# EDCPSUMK2-RP2040.net
KiCad netlist of a schematic drawn in EAGLE
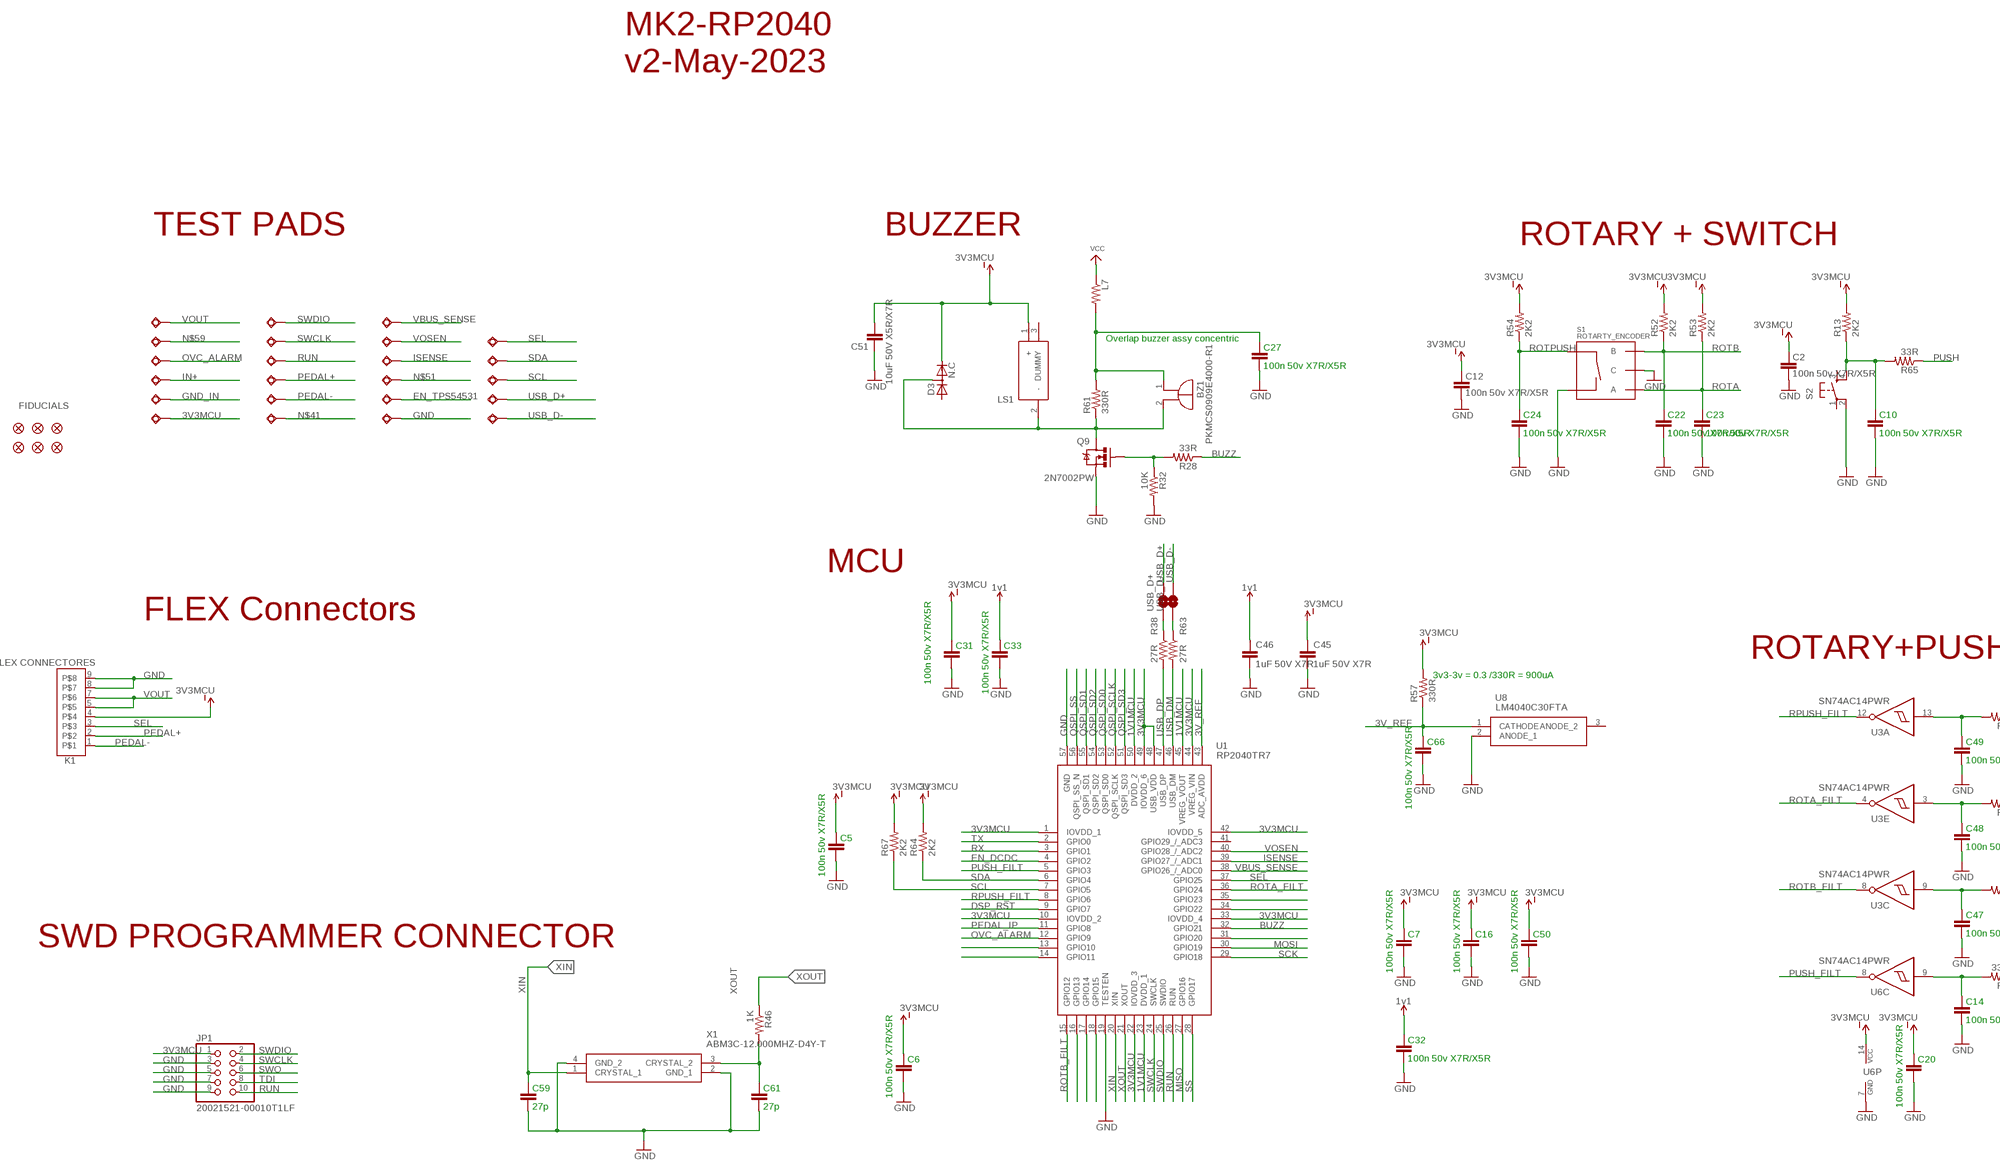
[diagram p0: schematic, sheet 1, part 1 of 3]
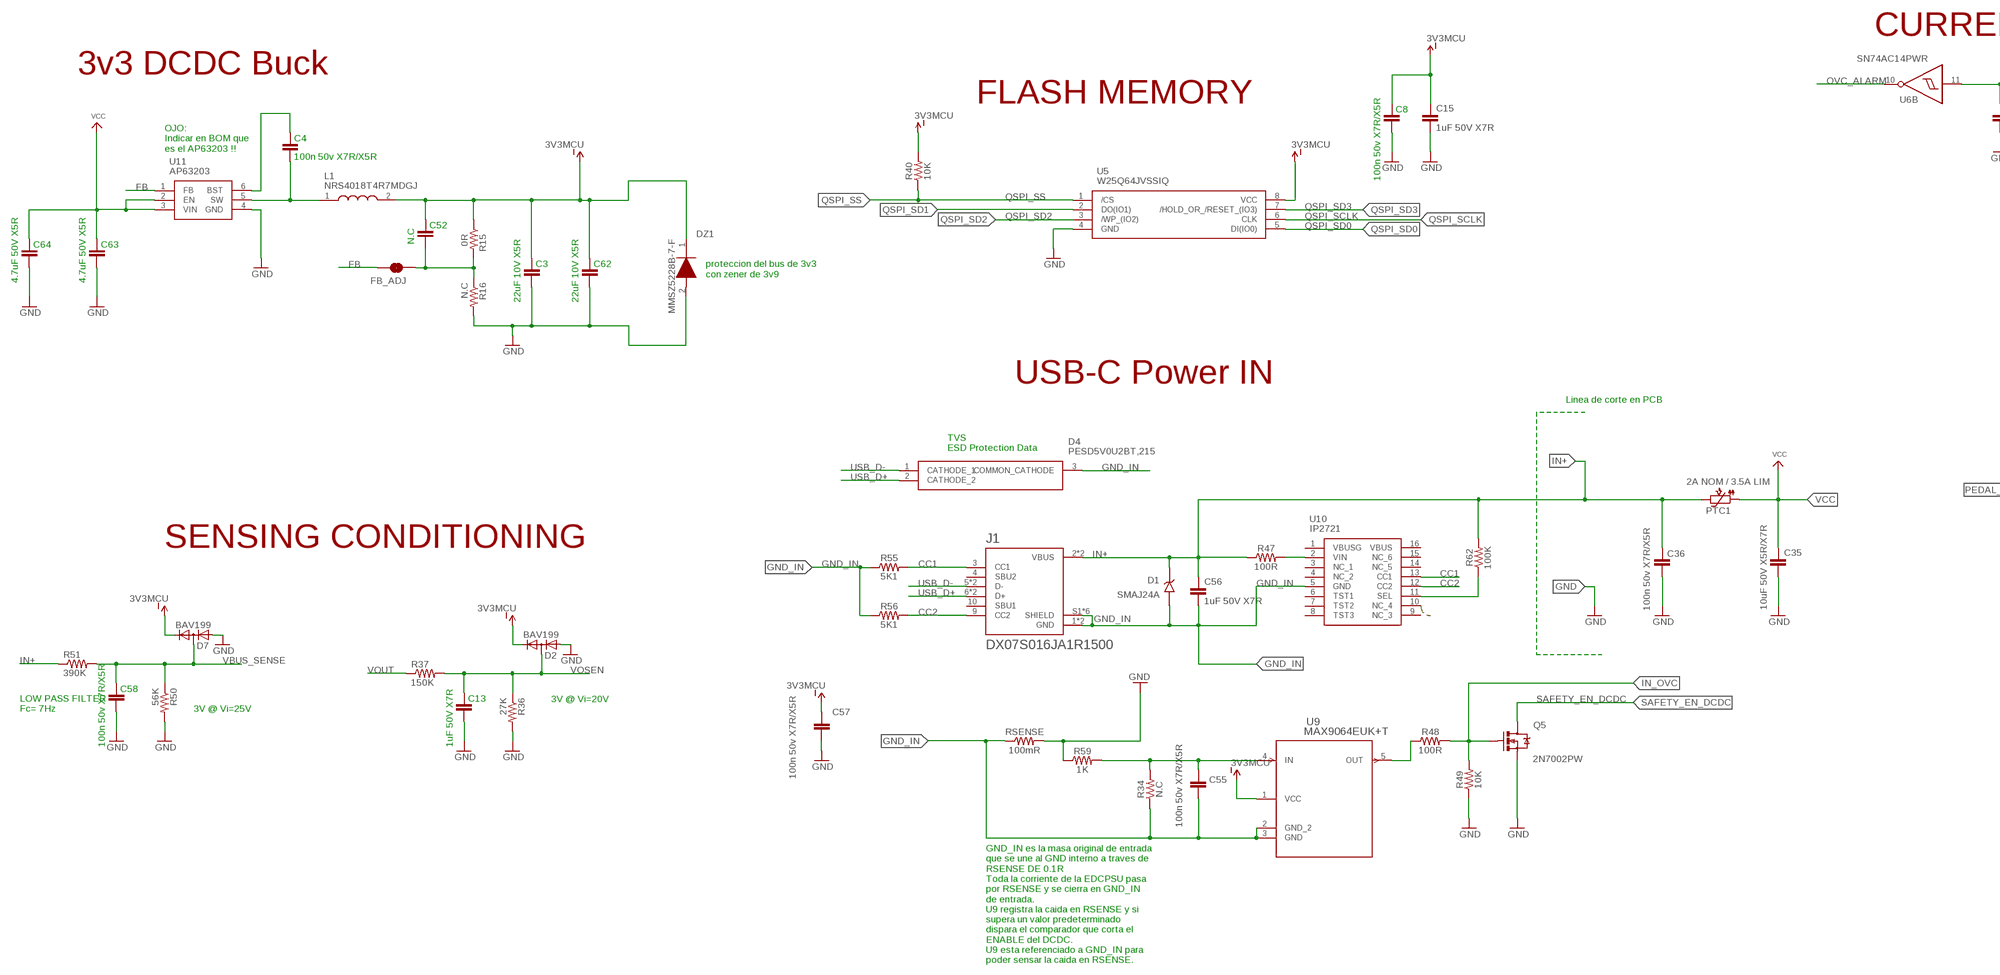
[diagram p1: schematic, sheet 1, part 2 of 3]
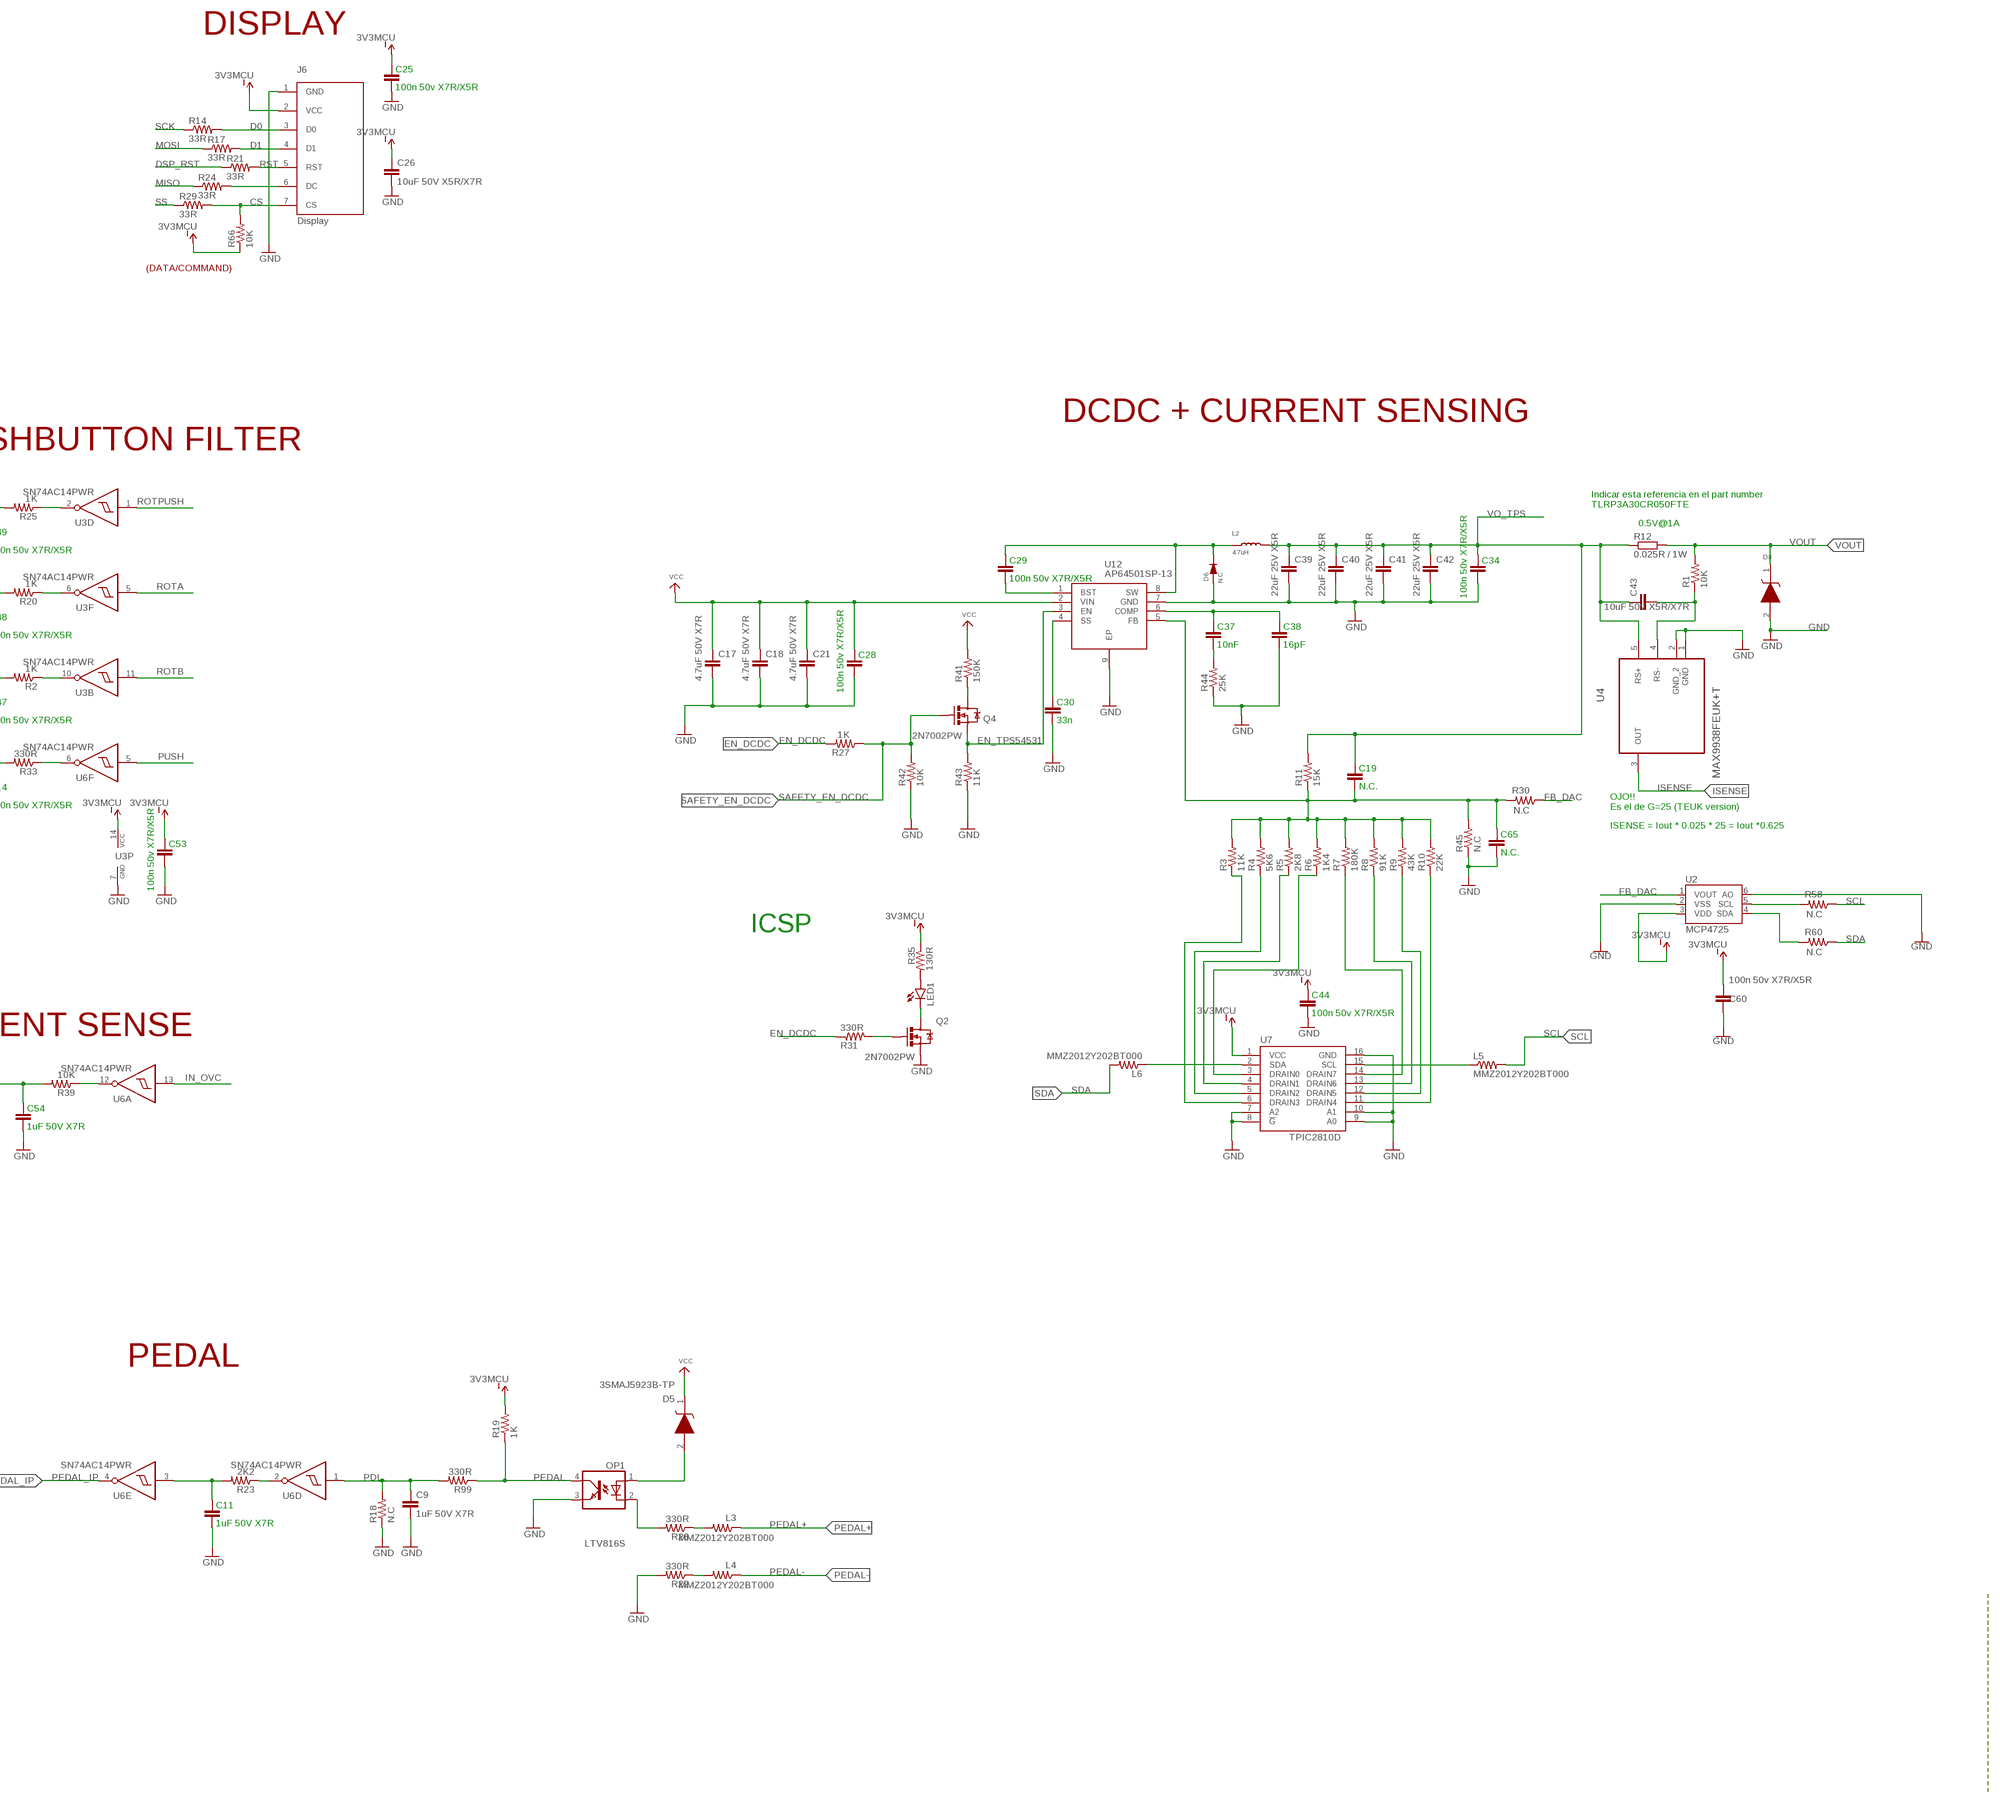
[diagram p2: schematic, sheet 1, part 3 of 3]

(export (version "E")
  (design (tool "Eeschema 10.0.6"))
  (components
    (comp (ref "3V3MCU")
      (value "TESTPAD_TPSQB1,27")
      (footprint "eagle-import:TESTPAD_B1,27")
      (libsource (lib "eagle-import") (part "TESTPAD_TPSQB1,27"))
    )
    (comp (ref "BZ1")
      (value "PKMCS0909E4000-R1")
      (footprint "eagle-import:PKMCS0909")
      (libsource (lib "eagle-import") (part "PKMCS0909E4000-R1"))
    )
    (comp (ref "C2")
      (value "100n 50v X7R/X5R")
      (footprint "eagle-import:0805")
      (libsource (lib "eagle-import") (part "CAP0805"))
    )
    (comp (ref "C3")
      (value "22uF 10V X5R")
      (footprint "eagle-import:0805")
      (libsource (lib "eagle-import") (part "CAP0805"))
    )
    (comp (ref "C4")
      (value "100n 50v X7R/X5R")
      (footprint "eagle-import:0805")
      (libsource (lib "eagle-import") (part "CAP0805"))
    )
    (comp (ref "C5")
      (value "100n 50v X7R/X5R")
      (footprint "eagle-import:0805")
      (libsource (lib "eagle-import") (part "CAP0805"))
    )
    (comp (ref "C6")
      (value "100n 50v X7R/X5R")
      (footprint "eagle-import:0805")
      (libsource (lib "eagle-import") (part "CAP0805"))
    )
    (comp (ref "C7")
      (value "100n 50v X7R/X5R")
      (footprint "eagle-import:0805")
      (libsource (lib "eagle-import") (part "CAP0805"))
    )
    (comp (ref "C8")
      (value "100n 50v X7R/X5R")
      (footprint "eagle-import:0805")
      (libsource (lib "eagle-import") (part "CAP0805"))
    )
    (comp (ref "C9")
      (value "1uF 50V X7R")
      (footprint "eagle-import:0805")
      (libsource (lib "eagle-import") (part "CAP0805"))
    )
    (comp (ref "C10")
      (value "100n 50v X7R/X5R")
      (footprint "eagle-import:0805")
      (libsource (lib "eagle-import") (part "CAP0805"))
    )
    (comp (ref "C11")
      (value "1uF 50V X7R")
      (footprint "eagle-import:0805")
      (libsource (lib "eagle-import") (part "CAP0805"))
    )
    (comp (ref "C12")
      (value "100n 50v X7R/X5R")
      (footprint "eagle-import:0805")
      (libsource (lib "eagle-import") (part "CAP0805"))
    )
    (comp (ref "C13")
      (value "1uF 50V X7R")
      (footprint "eagle-import:0805")
      (libsource (lib "eagle-import") (part "CAP0805"))
    )
    (comp (ref "C14")
      (value "100n 50v X7R/X5R")
      (footprint "eagle-import:0805")
      (libsource (lib "eagle-import") (part "CAP0805"))
    )
    (comp (ref "C15")
      (value "1uF 50V X7R")
      (footprint "eagle-import:0805")
      (libsource (lib "eagle-import") (part "CAP0805"))
    )
    (comp (ref "C16")
      (value "100n 50v X7R/X5R")
      (footprint "eagle-import:0805")
      (libsource (lib "eagle-import") (part "CAP0805"))
    )
    (comp (ref "C17")
      (value "4.7uF 50V X7R")
      (footprint "eagle-import:1210")
      (libsource (lib "eagle-import") (part "CAP1210"))
    )
    (comp (ref "C18")
      (value "4.7uF 50V X7R")
      (footprint "eagle-import:1210")
      (libsource (lib "eagle-import") (part "CAP1210"))
    )
    (comp (ref "C19")
      (value "N.C.")
      (footprint "eagle-import:0805")
      (libsource (lib "eagle-import") (part "CAP0805"))
    )
    (comp (ref "C20")
      (value "100n 50v X7R/X5R")
      (footprint "eagle-import:0805")
      (libsource (lib "eagle-import") (part "CAP0805"))
    )
    (comp (ref "C21")
      (value "4.7uF 50V X7R")
      (footprint "eagle-import:1210")
      (libsource (lib "eagle-import") (part "CAP1210"))
    )
    (comp (ref "C22")
      (value "100n 50v X7R/X5R")
      (footprint "eagle-import:0805")
      (libsource (lib "eagle-import") (part "CAP0805"))
    )
    (comp (ref "C23")
      (value "100n 50v X7R/X5R")
      (footprint "eagle-import:0805")
      (libsource (lib "eagle-import") (part "CAP0805"))
    )
    (comp (ref "C24")
      (value "100n 50v X7R/X5R")
      (footprint "eagle-import:0805")
      (libsource (lib "eagle-import") (part "CAP0805"))
    )
    (comp (ref "C25")
      (value "100n 50v X7R/X5R")
      (footprint "eagle-import:0805")
      (libsource (lib "eagle-import") (part "CAP0805"))
    )
    (comp (ref "C26")
      (value "10uF 50V X5R/X7R")
      (footprint "eagle-import:1206")
      (libsource (lib "eagle-import") (part "CAP1206"))
    )
    (comp (ref "C27")
      (value "100n 50v X7R/X5R")
      (footprint "eagle-import:0805")
      (libsource (lib "eagle-import") (part "CAP0805"))
    )
    (comp (ref "C28")
      (value "100n 50v X7R/X5R")
      (footprint "eagle-import:0805")
      (libsource (lib "eagle-import") (part "CAP0805"))
    )
    (comp (ref "C29")
      (value "100n 50v X7R/X5R")
      (footprint "eagle-import:0805")
      (libsource (lib "eagle-import") (part "CAP0805"))
    )
    (comp (ref "C30")
      (value "33n")
      (footprint "eagle-import:0805")
      (libsource (lib "eagle-import") (part "CAP0805"))
    )
    (comp (ref "C31")
      (value "100n 50v X7R/X5R")
      (footprint "eagle-import:0805")
      (libsource (lib "eagle-import") (part "CAP0805"))
    )
    (comp (ref "C32")
      (value "100n 50v X7R/X5R")
      (footprint "eagle-import:0805")
      (libsource (lib "eagle-import") (part "CAP0805"))
    )
    (comp (ref "C33")
      (value "100n 50v X7R/X5R")
      (footprint "eagle-import:0805")
      (libsource (lib "eagle-import") (part "CAP0805"))
    )
    (comp (ref "C34")
      (value "100n 50v X7R/X5R")
      (footprint "eagle-import:0805")
      (libsource (lib "eagle-import") (part "CAP0805"))
    )
    (comp (ref "C35")
      (value "10uF 50V X5R/X7R")
      (footprint "eagle-import:1206")
      (libsource (lib "eagle-import") (part "CAP1206"))
    )
    (comp (ref "C36")
      (value "100n 50v X7R/X5R")
      (footprint "eagle-import:0805")
      (libsource (lib "eagle-import") (part "CAP0805"))
    )
    (comp (ref "C37")
      (value "10nF")
      (footprint "eagle-import:0805")
      (libsource (lib "eagle-import") (part "CAP0805"))
    )
    (comp (ref "C38")
      (value "16pF")
      (footprint "eagle-import:0805")
      (libsource (lib "eagle-import") (part "CAP0805"))
    )
    (comp (ref "C39")
      (value "22uF 25V X5R")
      (footprint "eagle-import:1210")
      (libsource (lib "eagle-import") (part "CAP1210"))
    )
    (comp (ref "C40")
      (value "22uF 25V X5R")
      (footprint "eagle-import:1210")
      (libsource (lib "eagle-import") (part "CAP1210"))
    )
    (comp (ref "C41")
      (value "22uF 25V X5R")
      (footprint "eagle-import:1210")
      (libsource (lib "eagle-import") (part "CAP1210"))
    )
    (comp (ref "C42")
      (value "22uF 25V X5R")
      (footprint "eagle-import:1210")
      (libsource (lib "eagle-import") (part "CAP1210"))
    )
    (comp (ref "C43")
      (value "10uF 50V X5R/X7R")
      (footprint "eagle-import:1206")
      (libsource (lib "eagle-import") (part "CAP1206"))
    )
    (comp (ref "C44")
      (value "100n 50v X7R/X5R")
      (footprint "eagle-import:0805")
      (libsource (lib "eagle-import") (part "CAP0805"))
    )
    (comp (ref "C45")
      (value "1uF 50V X7R")
      (footprint "eagle-import:0805")
      (libsource (lib "eagle-import") (part "CAP0805"))
    )
    (comp (ref "C46")
      (value "1uF 50V X7R")
      (footprint "eagle-import:0805")
      (libsource (lib "eagle-import") (part "CAP0805"))
    )
    (comp (ref "C47")
      (value "100n 50v X7R/X5R")
      (footprint "eagle-import:0805")
      (libsource (lib "eagle-import") (part "CAP0805"))
    )
    (comp (ref "C48")
      (value "100n 50v X7R/X5R")
      (footprint "eagle-import:0805")
      (libsource (lib "eagle-import") (part "CAP0805"))
    )
    (comp (ref "C49")
      (value "100n 50v X7R/X5R")
      (footprint "eagle-import:0805")
      (libsource (lib "eagle-import") (part "CAP0805"))
    )
    (comp (ref "C50")
      (value "100n 50v X7R/X5R")
      (footprint "eagle-import:0805")
      (libsource (lib "eagle-import") (part "CAP0805"))
    )
    (comp (ref "C51")
      (value "10uF 50V X5R/X7R")
      (footprint "eagle-import:1206")
      (libsource (lib "eagle-import") (part "CAP1206"))
    )
    (comp (ref "C52")
      (value "N.C")
      (footprint "eagle-import:0805")
      (libsource (lib "eagle-import") (part "CAP0805"))
    )
    (comp (ref "C53")
      (value "100n 50v X7R/X5R")
      (footprint "eagle-import:0805")
      (libsource (lib "eagle-import") (part "CAP0805"))
    )
    (comp (ref "C54")
      (value "1uF 50V X7R")
      (footprint "eagle-import:0805")
      (libsource (lib "eagle-import") (part "CAP0805"))
    )
    (comp (ref "C55")
      (value "100n 50v X7R/X5R")
      (footprint "eagle-import:0805")
      (libsource (lib "eagle-import") (part "CAP0805"))
    )
    (comp (ref "C56")
      (value "1uF 50V X7R")
      (footprint "eagle-import:0805")
      (libsource (lib "eagle-import") (part "CAP0805"))
    )
    (comp (ref "C57")
      (value "100n 50v X7R/X5R")
      (footprint "eagle-import:0805")
      (libsource (lib "eagle-import") (part "CAP0805"))
    )
    (comp (ref "C58")
      (value "100n 50v X7R/X5R")
      (footprint "eagle-import:0805")
      (libsource (lib "eagle-import") (part "CAP0805"))
    )
    (comp (ref "C59")
      (value "27p")
      (footprint "eagle-import:0805")
      (libsource (lib "eagle-import") (part "CAP0805"))
    )
    (comp (ref "C60")
      (value "100n 50v X7R/X5R")
      (footprint "eagle-import:0805")
      (libsource (lib "eagle-import") (part "CAP0805"))
    )
    (comp (ref "C61")
      (value "27p")
      (footprint "eagle-import:0805")
      (libsource (lib "eagle-import") (part "CAP0805"))
    )
    (comp (ref "C62")
      (value "22uF 10V X5R")
      (footprint "eagle-import:0805")
      (libsource (lib "eagle-import") (part "CAP0805"))
    )
    (comp (ref "C63")
      (value "4.7uF 50V X5R")
      (footprint "eagle-import:0805")
      (libsource (lib "eagle-import") (part "CAP0805"))
    )
    (comp (ref "C64")
      (value "4.7uF 50V X5R")
      (footprint "eagle-import:0805")
      (libsource (lib "eagle-import") (part "CAP0805"))
    )
    (comp (ref "C65")
      (value "N.C.")
      (footprint "eagle-import:0805")
      (libsource (lib "eagle-import") (part "CAP0805"))
    )
    (comp (ref "C66")
      (value "100n 50v X7R/X5R")
      (footprint "eagle-import:0805")
      (libsource (lib "eagle-import") (part "CAP0805"))
    )
    (comp (ref "D1")
      (value "SMAJ24A")
      (footprint "eagle-import:DIOM4325X244N")
      (fields (field (name "MF") "Micro Commercial Components") (field (name "MP") "3SMAJ5934B"))
      (libsource (lib "eagle-import") (part "3SMAJ5934B"))
    )
    (comp (ref "D2")
      (value "BAV199")
      (footprint "eagle-import:SOT23")
      (libsource (lib "eagle-import") (part "BAV199"))
    )
    (comp (ref "D3")
      (value "N.C")
      (footprint "eagle-import:SOT23")
      (libsource (lib "eagle-import") (part "BAV199"))
    )
    (comp (ref "D4")
      (value "PESD5V0U2BT,215")
      (footprint "eagle-import:SOT95P230X110-3N")
      (fields (field (name "MOUSER_PART_NUMBER") "771-PESD5V0U2BTT/R"))
      (libsource (lib "eagle-import") (part "PESD5V0U2BT,215"))
    )
    (comp (ref "D5")
      (value "3SMAJ5923B-TP")
      (footprint "eagle-import:DIOM5226X244N")
      (fields (field (name "MOUSER_PART_NUMBER") "833-3SMAJ5923B-TP"))
      (libsource (lib "eagle-import") (part "3SMAJ5923B-TP"))
    )
    (comp (ref "D6")
      (value "N.C")
      (footprint "eagle-import:DO-214AB")
      (libsource (lib "eagle-import") (part "DSMC"))
    )
    (comp (ref "D7")
      (value "BAV199")
      (footprint "eagle-import:SOT23")
      (libsource (lib "eagle-import") (part "BAV199"))
    )
    (comp (ref "D8")
      (value "RB060M-60TR")
      (footprint "eagle-import:DIOM5226X244N")
      (fields
        (field (name "ARROW_PART_NUMBER") "3SMAJ5923B-TP")
        (field (name "MOUSER_PART_NUMBER") "833-3SMAJ5923B-TP")
      )
      (libsource (lib "eagle-import") (part "3SMAJ5923B-TP"))
    )
    (comp (ref "DZ1")
      (value "MMSZ5228B-7-F")
      (footprint "eagle-import:SODFL3518X115N")
      (libsource (lib "eagle-import") (part "MMSZ5228B-7-F"))
    )
    (comp (ref "EN_TPS54531")
      (value "TESTPAD_TPSQB1,27")
      (footprint "eagle-import:TESTPAD_B1,27")
      (libsource (lib "eagle-import") (part "TESTPAD_TPSQB1,27"))
    )
    (comp (ref "FB_ADJ")
      (value "JUMPER-SMT_2_NC_TRACE_NO-SILK")
      (footprint "eagle-import:SMT-JUMPER_2_NC_TRACE_NO-SILK")
      (libsource (lib "eagle-import") (part "JUMPER-SMT_2_NC_TRACE_NO-SILK"))
    )
    (comp (ref "FID1")
      (value "FIDUCIAL1X2")
      (footprint "eagle-import:FIDUCIAL-1X2")
      (libsource (lib "eagle-import") (part "FIDUCIAL1X2"))
    )
    (comp (ref "FID2")
      (value "FIDUCIAL1X2")
      (footprint "eagle-import:FIDUCIAL-1X2")
      (libsource (lib "eagle-import") (part "FIDUCIAL1X2"))
    )
    (comp (ref "FID3")
      (value "FIDUCIAL1X2")
      (footprint "eagle-import:FIDUCIAL-1X2")
      (libsource (lib "eagle-import") (part "FIDUCIAL1X2"))
    )
    (comp (ref "FID4")
      (value "FIDUCIAL1X2")
      (footprint "eagle-import:FIDUCIAL-1X2")
      (libsource (lib "eagle-import") (part "FIDUCIAL1X2"))
    )
    (comp (ref "FID5")
      (value "FIDUCIAL1X2")
      (footprint "eagle-import:FIDUCIAL-1X2")
      (libsource (lib "eagle-import") (part "FIDUCIAL1X2"))
    )
    (comp (ref "FID6")
      (value "FIDUCIAL1X2")
      (footprint "eagle-import:FIDUCIAL-1X2")
      (libsource (lib "eagle-import") (part "FIDUCIAL1X2"))
    )
    (comp (ref "GND")
      (value "TESTPAD_TPSQB1,27")
      (footprint "eagle-import:TESTPAD_B1,27")
      (libsource (lib "eagle-import") (part "TESTPAD_TPSQB1,27"))
    )
    (comp (ref "GND_IN")
      (value "TESTPAD_TPSQB1,27")
      (footprint "eagle-import:TESTPAD_B1,27")
      (libsource (lib "eagle-import") (part "TESTPAD_TPSQB1,27"))
    )
    (comp (ref "IN+")
      (value "TESTPAD_TPSQB1,27")
      (footprint "eagle-import:TESTPAD_B1,27")
      (libsource (lib "eagle-import") (part "TESTPAD_TPSQB1,27"))
    )
    (comp (ref "ISENSE")
      (value "TESTPAD_TPSQB1,27")
      (footprint "eagle-import:TESTPAD_B1,27")
      (libsource (lib "eagle-import") (part "TESTPAD_TPSQB1,27"))
    )
    (comp (ref "J1")
      (value "DX07S016JA1R1500")
      (footprint "eagle-import:JAE_DX07S016JA1R1500")
      (fields
        (field (name "DIGI-KEY_PART_NUMBER") "670-DX07S016JA1R1500CT-ND")
        (field (name "MF") "JAE Electronics")
      )
      (libsource (lib "eagle-import") (part "DX07S016JA1R1500"))
    )
    (comp (ref "J6")
      (value "Display")
      (footprint "eagle-import:OLED_LCD")
      (libsource (lib "eagle-import") (part "OLED_LCD"))
    )
    (comp (ref "JP1")
      (value "20021521-00010T1LF")
      (footprint "eagle-import:20021521-00010T1LF")
      (fields (field (name "DIGI-KEY_PART_NUMBER") "609-4054-ND") (field (name "MF") "AMPHENOL ICC / FCI"))
      (libsource (lib "eagle-import") (part "20021521-00010T1LF"))
    )
    (comp (ref "K1")
      (value "FLEX CONNECTORES")
      (footprint "eagle-import:FLEX8")
      (libsource (lib "eagle-import") (part "FLEX8"))
    )
    (comp (ref "L1")
      (value "NRS4018T4R7MDGJ")
      (footprint "eagle-import:NRS4018T100MDGJ")
      (fields (field (name "MOUSER_PART_NUMBER") "963-NRS4018T4R7MDGJ"))
      (libsource (lib "eagle-import") (part "NRS4018T4R7MDGJ"))
    )
    (comp (ref "L2")
      (value "4.7uH")
      (footprint "eagle-import:WE-LHMI")
      (libsource (lib "eagle-import") (part "L74437368047"))
    )
    (comp (ref "L3")
      (value "MMZ2012Y202BT000")
      (footprint "eagle-import:0805")
      (libsource (lib "eagle-import") (part "RESISTOR0805-RES"))
    )
    (comp (ref "L4")
      (value "MMZ2012Y202BT000")
      (footprint "eagle-import:0805")
      (libsource (lib "eagle-import") (part "RESISTOR0805-RES"))
    )
    (comp (ref "L5")
      (value "MMZ2012Y202BT000")
      (footprint "eagle-import:0805")
      (libsource (lib "eagle-import") (part "RESISTOR0805-RES"))
    )
    (comp (ref "L6")
      (value "MMZ2012Y202BT000")
      (footprint "eagle-import:0805")
      (libsource (lib "eagle-import") (part "RESISTOR0805-RES"))
    )
    (comp (ref "L7")
      (value "MMZ2012Y202BT000")
      (footprint "eagle-import:0805")
      (libsource (lib "eagle-import") (part "RESISTOR0805-RES"))
    )
    (comp (ref "LED1")
      (value "LED3MM")
      (footprint "eagle-import:LED3MM")
      (libsource (lib "eagle-import") (part "LED3MM"))
    )
    (comp (ref "LS1")
      (value "SMT-0540-S-R")
      (footprint "eagle-import:SMT0540SR")
      (fields (field (name "MOUSER_PART_NUMBER") "665-SMT0540SR"))
      (libsource (lib "eagle-import") (part "SMT-0540-S-R"))
    )
    (comp (ref "N$41")
      (value "TESTPAD_TPSQB1,27")
      (footprint "eagle-import:TESTPAD_B1,27")
      (libsource (lib "eagle-import") (part "TESTPAD_TPSQB1,27"))
    )
    (comp (ref "N$51")
      (value "TESTPAD_TPSQB1,27")
      (footprint "eagle-import:TESTPAD_B1,27")
      (libsource (lib "eagle-import") (part "TESTPAD_TPSQB1,27"))
    )
    (comp (ref "N$59")
      (value "TESTPAD_TPSQB1,27")
      (footprint "eagle-import:TESTPAD_B1,27")
      (libsource (lib "eagle-import") (part "TESTPAD_TPSQB1,27"))
    )
    (comp (ref "OP1")
      (value "LTV816S")
      (footprint "eagle-import:SMD4")
      (libsource (lib "eagle-import") (part "LTV816S"))
    )
    (comp (ref "OVC_ALARM")
      (value "TESTPAD_TPSQB1,27")
      (footprint "eagle-import:TESTPAD_B1,27")
      (libsource (lib "eagle-import") (part "TESTPAD_TPSQB1,27"))
    )
    (comp (ref "PEDAL+")
      (value "TESTPAD_TPSQB1,27")
      (footprint "eagle-import:TESTPAD_B1,27")
      (libsource (lib "eagle-import") (part "TESTPAD_TPSQB1,27"))
    )
    (comp (ref "PEDAL-")
      (value "TESTPAD_TPSQB1,27")
      (footprint "eagle-import:TESTPAD_B1,27")
      (libsource (lib "eagle-import") (part "TESTPAD_TPSQB1,27"))
    )
    (comp (ref "PTC1")
      (value "2A NOM / 3.5A LIM")
      (footprint "eagle-import:1812L")
      (libsource (lib "eagle-import") (part "PTC-"))
    )
    (comp (ref "Q2")
      (value "2N7002PW")
      (footprint "eagle-import:SOT323")
      (libsource (lib "eagle-import") (part "MOSFET-NCHANNEL2N7002PW"))
    )
    (comp (ref "Q4")
      (value "2N7002PW")
      (footprint "eagle-import:SOT323")
      (libsource (lib "eagle-import") (part "MOSFET-NCHANNEL2N7002PW"))
    )
    (comp (ref "Q5")
      (value "2N7002PW")
      (footprint "eagle-import:SOT323")
      (libsource (lib "eagle-import") (part "MOSFET-NCHANNEL2N7002PW"))
    )
    (comp (ref "Q9")
      (value "2N7002PW")
      (footprint "eagle-import:SOT323")
      (libsource (lib "eagle-import") (part "MOSFET-NCHANNEL2N7002PW"))
    )
    (comp (ref "R1")
      (value "10K")
      (footprint "eagle-import:0805")
      (libsource (lib "eagle-import") (part "RESISTOR0805"))
    )
    (comp (ref "R2")
      (value "1K")
      (footprint "eagle-import:0805")
      (libsource (lib "eagle-import") (part "RESISTOR0805"))
    )
    (comp (ref "R3")
      (value "11K")
      (footprint "eagle-import:0805")
      (libsource (lib "eagle-import") (part "RESISTOR0805"))
    )
    (comp (ref "R4")
      (value "5K6")
      (footprint "eagle-import:0805")
      (libsource (lib "eagle-import") (part "RESISTOR0805"))
    )
    (comp (ref "R5")
      (value "2K8")
      (footprint "eagle-import:0805")
      (libsource (lib "eagle-import") (part "RESISTOR0805"))
    )
    (comp (ref "R6")
      (value "1K4")
      (footprint "eagle-import:0805")
      (libsource (lib "eagle-import") (part "RESISTOR0805"))
    )
    (comp (ref "R7")
      (value "180K")
      (footprint "eagle-import:0805")
      (libsource (lib "eagle-import") (part "RESISTOR0805"))
    )
    (comp (ref "R8")
      (value "91K")
      (footprint "eagle-import:0805")
      (libsource (lib "eagle-import") (part "RESISTOR0805"))
    )
    (comp (ref "R9")
      (value "43K")
      (footprint "eagle-import:0805")
      (libsource (lib "eagle-import") (part "RESISTOR0805"))
    )
    (comp (ref "R10")
      (value "22K")
      (footprint "eagle-import:0805")
      (libsource (lib "eagle-import") (part "RESISTOR0805"))
    )
    (comp (ref "R11")
      (value "15K")
      (footprint "eagle-import:0805")
      (libsource (lib "eagle-import") (part "RESISTOR0805"))
    )
    (comp (ref "R12")
      (value "0.025R / 1W")
      (footprint "eagle-import:R2512")
      (libsource (lib "eagle-import") (part "RR2512"))
    )
    (comp (ref "R13")
      (value "2K2")
      (footprint "eagle-import:0805")
      (libsource (lib "eagle-import") (part "RESISTOR0805"))
    )
    (comp (ref "R14")
      (value "33R")
      (footprint "eagle-import:0805")
      (libsource (lib "eagle-import") (part "RESISTOR0805"))
    )
    (comp (ref "R15")
      (value "0R")
      (footprint "eagle-import:0805")
      (libsource (lib "eagle-import") (part "RESISTOR0805"))
    )
    (comp (ref "R16")
      (value "N.C")
      (footprint "eagle-import:0805")
      (libsource (lib "eagle-import") (part "RESISTOR0805"))
    )
    (comp (ref "R17")
      (value "33R")
      (footprint "eagle-import:0805")
      (libsource (lib "eagle-import") (part "RESISTOR0805"))
    )
    (comp (ref "R18")
      (value "N.C")
      (footprint "eagle-import:0805")
      (libsource (lib "eagle-import") (part "RESISTOR0805"))
    )
    (comp (ref "R19")
      (value "1K")
      (footprint "eagle-import:0805")
      (libsource (lib "eagle-import") (part "RESISTOR0805"))
    )
    (comp (ref "R20")
      (value "1K")
      (footprint "eagle-import:0805")
      (libsource (lib "eagle-import") (part "RESISTOR0805"))
    )
    (comp (ref "R21")
      (value "33R")
      (footprint "eagle-import:0805")
      (libsource (lib "eagle-import") (part "RESISTOR0805"))
    )
    (comp (ref "R22")
      (value "330R")
      (footprint "eagle-import:0805")
      (libsource (lib "eagle-import") (part "RESISTOR0805"))
    )
    (comp (ref "R23")
      (value "2K2")
      (footprint "eagle-import:0805")
      (libsource (lib "eagle-import") (part "RESISTOR0805"))
    )
    (comp (ref "R24")
      (value "33R")
      (footprint "eagle-import:0805")
      (libsource (lib "eagle-import") (part "RESISTOR0805"))
    )
    (comp (ref "R25")
      (value "1K")
      (footprint "eagle-import:0805")
      (libsource (lib "eagle-import") (part "RESISTOR0805"))
    )
    (comp (ref "R26")
      (value "330R")
      (footprint "eagle-import:0805")
      (libsource (lib "eagle-import") (part "RESISTOR0805"))
    )
    (comp (ref "R27")
      (value "1K")
      (footprint "eagle-import:0805")
      (libsource (lib "eagle-import") (part "RESISTOR0805"))
    )
    (comp (ref "R28")
      (value "33R")
      (footprint "eagle-import:0805")
      (libsource (lib "eagle-import") (part "RESISTOR0805"))
    )
    (comp (ref "R29")
      (value "33R")
      (footprint "eagle-import:0805")
      (libsource (lib "eagle-import") (part "RESISTOR0805"))
    )
    (comp (ref "R30")
      (value "N.C")
      (footprint "eagle-import:0805")
      (libsource (lib "eagle-import") (part "RESISTOR0805"))
    )
    (comp (ref "R31")
      (value "330R")
      (footprint "eagle-import:0805")
      (libsource (lib "eagle-import") (part "RESISTOR0805"))
    )
    (comp (ref "R32")
      (value "10K")
      (footprint "eagle-import:0805")
      (libsource (lib "eagle-import") (part "RESISTOR0805"))
    )
    (comp (ref "R33")
      (value "330R")
      (footprint "eagle-import:0805")
      (libsource (lib "eagle-import") (part "RESISTOR0805"))
    )
    (comp (ref "R34")
      (value "N.C")
      (footprint "eagle-import:0805")
      (libsource (lib "eagle-import") (part "RESISTOR0805"))
    )
    (comp (ref "R35")
      (value "130R")
      (footprint "eagle-import:0805")
      (libsource (lib "eagle-import") (part "RESISTOR0805"))
    )
    (comp (ref "R36")
      (value "27K")
      (footprint "eagle-import:0805")
      (libsource (lib "eagle-import") (part "RESISTOR0805"))
    )
    (comp (ref "R37")
      (value "150K")
      (footprint "eagle-import:0805")
      (libsource (lib "eagle-import") (part "RESISTOR0805"))
    )
    (comp (ref "R38")
      (value "27R")
      (footprint "eagle-import:0805")
      (libsource (lib "eagle-import") (part "RESISTOR0805"))
    )
    (comp (ref "R39")
      (value "10K")
      (footprint "eagle-import:0805")
      (libsource (lib "eagle-import") (part "RESISTOR0805"))
    )
    (comp (ref "R40")
      (value "10K")
      (footprint "eagle-import:0805")
      (libsource (lib "eagle-import") (part "RESISTOR0805"))
    )
    (comp (ref "R41")
      (value "150K")
      (footprint "eagle-import:0805")
      (libsource (lib "eagle-import") (part "RESISTOR0805"))
    )
    (comp (ref "R42")
      (value "10K")
      (footprint "eagle-import:0805")
      (libsource (lib "eagle-import") (part "RESISTOR0805"))
    )
    (comp (ref "R43")
      (value "11K")
      (footprint "eagle-import:0805")
      (libsource (lib "eagle-import") (part "RESISTOR0805"))
    )
    (comp (ref "R44")
      (value "25K")
      (footprint "eagle-import:0805")
      (libsource (lib "eagle-import") (part "RESISTOR0805"))
    )
    (comp (ref "R45")
      (value "N.C")
      (footprint "eagle-import:0805")
      (libsource (lib "eagle-import") (part "RESISTOR0805"))
    )
    (comp (ref "R46")
      (value "1K")
      (footprint "eagle-import:0805")
      (libsource (lib "eagle-import") (part "RESISTOR0805"))
    )
    (comp (ref "R47")
      (value "100R")
      (footprint "eagle-import:0805")
      (libsource (lib "eagle-import") (part "RESISTOR0805"))
    )
    (comp (ref "R48")
      (value "100R")
      (footprint "eagle-import:0805")
      (libsource (lib "eagle-import") (part "RESISTOR0805"))
    )
    (comp (ref "R49")
      (value "10K")
      (footprint "eagle-import:0805")
      (libsource (lib "eagle-import") (part "RESISTOR0805"))
    )
    (comp (ref "R50")
      (value "56K")
      (footprint "eagle-import:0805")
      (libsource (lib "eagle-import") (part "RESISTOR0805"))
    )
    (comp (ref "R51")
      (value "390K")
      (footprint "eagle-import:0805")
      (libsource (lib "eagle-import") (part "RESISTOR0805"))
    )
    (comp (ref "R52")
      (value "2K2")
      (footprint "eagle-import:0805")
      (libsource (lib "eagle-import") (part "RESISTOR0805"))
    )
    (comp (ref "R53")
      (value "2K2")
      (footprint "eagle-import:0805")
      (libsource (lib "eagle-import") (part "RESISTOR0805"))
    )
    (comp (ref "R54")
      (value "2K2")
      (footprint "eagle-import:0805")
      (libsource (lib "eagle-import") (part "RESISTOR0805"))
    )
    (comp (ref "R55")
      (value "5K1")
      (footprint "eagle-import:0805")
      (libsource (lib "eagle-import") (part "RESISTOR0805"))
    )
    (comp (ref "R56")
      (value "5K1")
      (footprint "eagle-import:0805")
      (libsource (lib "eagle-import") (part "RESISTOR0805"))
    )
    (comp (ref "R57")
      (value "330R")
      (footprint "eagle-import:0805")
      (libsource (lib "eagle-import") (part "RESISTOR0805"))
    )
    (comp (ref "R58")
      (value "N.C")
      (footprint "eagle-import:0805")
      (libsource (lib "eagle-import") (part "RESISTOR0805"))
    )
    (comp (ref "R59")
      (value "1K")
      (footprint "eagle-import:0805")
      (libsource (lib "eagle-import") (part "RESISTOR0805"))
    )
    (comp (ref "R60")
      (value "N.C")
      (footprint "eagle-import:0805")
      (libsource (lib "eagle-import") (part "RESISTOR0805"))
    )
    (comp (ref "R61")
      (value "330R")
      (footprint "eagle-import:0805")
      (libsource (lib "eagle-import") (part "RESISTOR0805"))
    )
    (comp (ref "R62")
      (value "100K")
      (footprint "eagle-import:0805")
      (libsource (lib "eagle-import") (part "RESISTOR0805"))
    )
    (comp (ref "R63")
      (value "27R")
      (footprint "eagle-import:0805")
      (libsource (lib "eagle-import") (part "RESISTOR0805"))
    )
    (comp (ref "R64")
      (value "2K2")
      (footprint "eagle-import:0805")
      (libsource (lib "eagle-import") (part "RESISTOR0805"))
    )
    (comp (ref "R65")
      (value "33R")
      (footprint "eagle-import:0805")
      (libsource (lib "eagle-import") (part "RESISTOR0805"))
    )
    (comp (ref "R66")
      (value "10K")
      (footprint "eagle-import:0805")
      (libsource (lib "eagle-import") (part "RESISTOR0805"))
    )
    (comp (ref "R67")
      (value "2K2")
      (footprint "eagle-import:0805")
      (libsource (lib "eagle-import") (part "RESISTOR0805"))
    )
    (comp (ref "R99")
      (value "330R")
      (footprint "eagle-import:0805")
      (libsource (lib "eagle-import") (part "RESISTOR0805"))
    )
    (comp (ref "RSENSE")
      (value "100mR")
      (footprint "eagle-import:1206")
      (libsource (lib "eagle-import") (part "SparkFun-Resistors_532_RESISTOR1206"))
    )
    (comp (ref "RUN")
      (value "TESTPAD_TPSQB1,27")
      (footprint "eagle-import:TESTPAD_B1,27")
      (libsource (lib "eagle-import") (part "TESTPAD_TPSQB1,27"))
    )
    (comp (ref "S1")
      (value "ROTARTY_ENCODER")
      (footprint "eagle-import:ROTARY_ENC_PLAIN")
      (libsource (lib "eagle-import") (part "ROTARTY_ENCODER"))
    )
    (comp (ref "S2")
      (value "TAC_SWITCH_KSC931G-SMD")
      (footprint "eagle-import:TAC_SW_SMD_KSC931G")
      (libsource (lib "eagle-import") (part "TAC_SWITCH_KSC931G-SMD"))
    )
    (comp (ref "SCL")
      (value "TESTPAD_TPSQB1,27")
      (footprint "eagle-import:TESTPAD_B1,27")
      (libsource (lib "eagle-import") (part "TESTPAD_TPSQB1,27"))
    )
    (comp (ref "SDA")
      (value "TESTPAD_TPSQB1,27")
      (footprint "eagle-import:TESTPAD_B1,27")
      (libsource (lib "eagle-import") (part "TESTPAD_TPSQB1,27"))
    )
    (comp (ref "SEL")
      (value "TESTPAD_TPSQB1,27")
      (footprint "eagle-import:TESTPAD_B1,27")
      (libsource (lib "eagle-import") (part "TESTPAD_TPSQB1,27"))
    )
    (comp (ref "SWCLK")
      (value "TESTPAD_TPSQB1,27")
      (footprint "eagle-import:TESTPAD_B1,27")
      (libsource (lib "eagle-import") (part "TESTPAD_TPSQB1,27"))
    )
    (comp (ref "SWDIO")
      (value "TESTPAD_TPSQB1,27")
      (footprint "eagle-import:TESTPAD_B1,27")
      (libsource (lib "eagle-import") (part "TESTPAD_TPSQB1,27"))
    )
    (comp (ref "U1")
      (value "RP2040TR7")
      (footprint "eagle-import:RP2040TR7")
      (libsource (lib "eagle-import") (part "RP2040TR7"))
    )
    (comp (ref "U2")
      (value "MCP4725")
      (footprint "eagle-import:SOT23-6")
      (libsource (lib "eagle-import") (part "MCP4725SOT-23"))
    )
    (comp (ref "U3")
      (value "SN74AC14PWR")
      (footprint "eagle-import:TSSOP14")
      (libsource (lib "eagle-import") (part "7414"))
    )
    (comp (ref "U4")
      (value "MAX9938FEUK+T")
      (footprint "eagle-import:SOT95P280X145-5N")
      (libsource (lib "eagle-import") (part "MAX9938FEUK+T"))
    )
    (comp (ref "U5")
      (value "W25Q64JVSSIQ")
      (footprint "eagle-import:SOIC127P790X216-8N")
      (fields (field (name "MOUSER_PART_NUMBER") "454-W25Q64JVSSIQ"))
      (libsource (lib "eagle-import") (part "W25Q64JVSSIQ"))
    )
    (comp (ref "U6")
      (value "SN74AC14PWR")
      (footprint "eagle-import:TSSOP14")
      (libsource (lib "eagle-import") (part "7414"))
    )
    (comp (ref "U7")
      (value "TPIC2810D")
      (footprint "eagle-import:SO16")
      (libsource (lib "eagle-import") (part "TPIC2810D"))
    )
    (comp (ref "U8")
      (value "LM4040C30FTA")
      (footprint "eagle-import:SOT96P240X120-3N")
      (fields (field (name "MOUSER_PART_NUMBER") "621-LM4040C30FTA"))
      (libsource (lib "eagle-import") (part "LM4040C30FTA"))
    )
    (comp (ref "U9")
      (value "MAX9064EUK+T")
      (footprint "eagle-import:21-0057F_MXM")
      (fields (field (name "COPYRIGHT") "Copyright (C) 2022 Ultra Librarian. All rights reserved."))
      (libsource (lib "eagle-import") (part "MAX9064EUK+T"))
    )
    (comp (ref "U10")
      (value "IP2721")
      (footprint "eagle-import:SOP65P640X120-16N")
      (libsource (lib "eagle-import") (part "IP2721"))
    )
    (comp (ref "U11")
      (value "AP63203")
      (footprint "eagle-import:SOT95P280X100-6N")
      (fields
        (field (name "ARROW_PART_NUMBER") "AP63201WU-7")
        (field (name "MOUSER_PART_NUMBER") "621-AP63201WU-7")
      )
      (libsource (lib "eagle-import") (part "AP63201WU-7"))
    )
    (comp (ref "U12")
      (value "AP64501SP-13")
      (footprint "eagle-import:SOIC127P600X163-9N")
      (fields (field (name "MOUSER_PART_NUMBER") "621-AP64501SP-13"))
      (libsource (lib "eagle-import") (part "AP64501SP-13"))
    )
    (comp (ref "USB-D+")
      (value "TESTPAD_TPSQB1,27")
      (footprint "eagle-import:TESTPAD_B1,27")
      (libsource (lib "eagle-import") (part "TESTPAD_TPSQB1,27"))
    )
    (comp (ref "USB-D-")
      (value "TESTPAD_TPSQB1,27")
      (footprint "eagle-import:TESTPAD_B1,27")
      (libsource (lib "eagle-import") (part "TESTPAD_TPSQB1,27"))
    )
    (comp (ref "USB_D+")
      (value "JUMPER-SMT_2_NO_NO-SILK")
      (footprint "eagle-import:SMT-JUMPER_2_NO_NO-SILK")
      (libsource (lib "eagle-import") (part "JUMPER-SMT_2_NO_NO-SILK"))
    )
    (comp (ref "USB_D-")
      (value "JUMPER-SMT_2_NO_NO-SILK")
      (footprint "eagle-import:SMT-JUMPER_2_NO_NO-SILK")
      (libsource (lib "eagle-import") (part "JUMPER-SMT_2_NO_NO-SILK"))
    )
    (comp (ref "VBUS_SENSE")
      (value "TESTPAD_TPSQB1,27")
      (footprint "eagle-import:TESTPAD_B1,27")
      (libsource (lib "eagle-import") (part "TESTPAD_TPSQB1,27"))
    )
    (comp (ref "VOSEN")
      (value "TESTPAD_TPSQB1,27")
      (footprint "eagle-import:TESTPAD_B1,27")
      (libsource (lib "eagle-import") (part "TESTPAD_TPSQB1,27"))
    )
    (comp (ref "VOUT")
      (value "TESTPAD_TPSQB1,27")
      (footprint "eagle-import:TESTPAD_B1,27")
      (libsource (lib "eagle-import") (part "TESTPAD_TPSQB1,27"))
    )
    (comp (ref "X1")
      (value "ABM3C-12.000MHZ-D4Y-T")
      (footprint "eagle-import:ABM3C16000MHZD4YT")
      (fields (field (name "MOUSER_PART_NUMBER") "815-ABM3C-12-D4YT"))
      (libsource (lib "eagle-import") (part "ABM3C-12.000MHZ-D4Y-T"))
    )
  )
  (nets
    (net (code "1") (name "/3V_REF") (class "Default")
      (node (ref "C66") (pin "2") (pinfunction "2_2") (pintype "passive"))
      (node (ref "R57") (pin "1") (pinfunction "1_1") (pintype "passive"))
      (node (ref "U1") (pin "43") (pinfunction "ADC_AVDD_43") (pintype "bidirectional"))
      (node (ref "U8") (pin "1") (pinfunction "CATHODE_1") (pintype "bidirectional"))
    )
    (net (code "2") (name "/BUZZ") (class "Default")
      (node (ref "R28") (pin "1") (pinfunction "1_1") (pintype "passive"))
      (node (ref "U1") (pin "32") (pinfunction "GPIO21_32") (pintype "bidirectional"))
    )
    (net (code "3") (name "/CC1") (class "Default")
      (node (ref "J1") (pin "3") (pinfunction "CC1_3") (pintype "passive"))
      (node (ref "R55") (pin "2") (pinfunction "2_2") (pintype "passive"))
      (node (ref "U10") (pin "13") (pinfunction "CC1_13") (pintype "bidirectional"))
    )
    (net (code "4") (name "/CC2") (class "Default")
      (node (ref "J1") (pin "9") (pinfunction "CC2_9") (pintype "passive"))
      (node (ref "R56") (pin "2") (pinfunction "2_2") (pintype "passive"))
      (node (ref "U10") (pin "12") (pinfunction "CC2_12") (pintype "bidirectional"))
    )
    (net (code "5") (name "/CS") (class "Default")
      (node (ref "J6") (pin "7") (pinfunction "CS_7") (pintype "bidirectional"))
      (node (ref "R29") (pin "2") (pinfunction "2_2") (pintype "passive"))
      (node (ref "R66") (pin "2") (pinfunction "2_2") (pintype "passive"))
    )
    (net (code "6") (name "/D0") (class "Default")
      (node (ref "J6") (pin "3") (pinfunction "D0_3") (pintype "bidirectional"))
      (node (ref "R14") (pin "2") (pinfunction "2_2") (pintype "passive"))
    )
    (net (code "7") (name "/D1") (class "Default")
      (node (ref "J6") (pin "4") (pinfunction "D1_4") (pintype "bidirectional"))
      (node (ref "R17") (pin "2") (pinfunction "2_2") (pintype "passive"))
    )
    (net (code "8") (name "/DSP_RST") (class "Default")
      (node (ref "R21") (pin "1") (pinfunction "1_1") (pintype "passive"))
      (node (ref "U1") (pin "9") (pinfunction "GPIO7_9") (pintype "bidirectional"))
    )
    (net (code "9") (name "/EN_TPS54531") (class "Default")
      (node (ref "EN_TPS54531") (pin "TP") (pinfunction "TP_TP") (pintype "input"))
      (node (ref "Q4") (pin "2") (pinfunction "S_2") (pintype "passive"))
      (node (ref "R43") (pin "2") (pinfunction "2_2") (pintype "passive"))
      (node (ref "U12") (pin "3") (pinfunction "EN_3") (pintype "bidirectional"))
    )
    (net (code "10") (name "/FB") (class "Default")
      (node (ref "FB_ADJ") (pin "2") (pinfunction "2_2") (pintype "passive"))
      (node (ref "U11") (pin "1") (pinfunction "FB_1") (pintype "bidirectional"))
    )
    (net (code "11") (name "/FB_DAC") (class "Default")
      (node (ref "R30") (pin "1") (pinfunction "1_1") (pintype "passive"))
      (node (ref "U2") (pin "1") (pinfunction "VOUT_1") (pintype "bidirectional"))
    )
    (net (code "12") (name "/MISO") (class "Default")
      (node (ref "R24") (pin "1") (pinfunction "1_1") (pintype "passive"))
      (node (ref "U1") (pin "27") (pinfunction "GPIO16_27") (pintype "bidirectional"))
    )
    (net (code "13") (name "/MOSI") (class "Default")
      (node (ref "R17") (pin "1") (pinfunction "1_1") (pintype "passive"))
      (node (ref "U1") (pin "30") (pinfunction "GPIO19_30") (pintype "bidirectional"))
    )
    (net (code "14") (name "/N$41") (class "Default")
      (node (ref "N$41") (pin "TP") (pinfunction "TP_TP") (pintype "input"))
      (node (ref "OP1") (pin "2") (pinfunction "C_2") (pintype "passive"))
      (node (ref "R26") (pin "2") (pinfunction "2_2") (pintype "passive"))
    )
    (net (code "15") (name "/N$51") (class "Default")
      (node (ref "C29") (pin "2") (pinfunction "2_2") (pintype "passive"))
      (node (ref "D6") (pin "2") (pinfunction "K_2") (pintype "bidirectional"))
      (node (ref "L2") (pin "1") (pinfunction "1_1") (pintype "passive"))
      (node (ref "N$51") (pin "TP") (pinfunction "TP_TP") (pintype "input"))
      (node (ref "U12") (pin "8") (pinfunction "SW_8") (pintype "bidirectional"))
    )
    (net (code "16") (name "/N$59") (class "Default")
      (node (ref "C55") (pin "1") (pinfunction "1_1") (pintype "passive"))
      (node (ref "N$59") (pin "TP") (pinfunction "TP_TP") (pintype "input"))
      (node (ref "R34") (pin "2") (pinfunction "2_2") (pintype "passive"))
      (node (ref "R59") (pin "2") (pinfunction "2_2") (pintype "passive"))
      (node (ref "U9") (pin "4") (pinfunction "IN_4") (pintype "input"))
    )
    (net (code "17") (name "/OVC_ALARM") (class "Default")
      (node (ref "OVC_ALARM") (pin "TP") (pinfunction "TP_TP") (pintype "input"))
      (node (ref "U1") (pin "12") (pinfunction "GPIO9_12") (pintype "bidirectional"))
      (node (ref "U6") (pin "10") (pinfunction "O_10") (pintype "output"))
    )
    (net (code "18") (name "/PDL") (class "Default")
      (node (ref "C9") (pin "1") (pinfunction "1_1") (pintype "passive"))
      (node (ref "R18") (pin "2") (pinfunction "2_2") (pintype "passive"))
      (node (ref "R99") (pin "2") (pinfunction "2_2") (pintype "passive"))
      (node (ref "U6") (pin "1") (pinfunction "I_1") (pintype "input"))
    )
    (net (code "19") (name "/PEDAL") (class "Default")
      (node (ref "OP1") (pin "4") (pinfunction "COL_4") (pintype "passive"))
      (node (ref "R19") (pin "1") (pinfunction "1_1") (pintype "passive"))
      (node (ref "R99") (pin "1") (pinfunction "1_1") (pintype "passive"))
    )
    (net (code "20") (name "/PUSH") (class "Default")
      (node (ref "R65") (pin "1") (pinfunction "1_1") (pintype "passive"))
      (node (ref "U6") (pin "5") (pinfunction "I_5") (pintype "input"))
    )
    (net (code "21") (name "/PUSH_FILT") (class "Default")
      (node (ref "U1") (pin "5") (pinfunction "GPIO3_5") (pintype "bidirectional"))
      (node (ref "U6") (pin "8") (pinfunction "O_8") (pintype "output"))
    )
    (net (code "22") (name "/ROTA") (class "Default")
      (node (ref "C23") (pin "2") (pinfunction "2_2") (pintype "passive"))
      (node (ref "R53") (pin "1") (pinfunction "1_1") (pintype "passive"))
      (node (ref "S1") (pin "A") (pinfunction "A_A") (pintype "bidirectional"))
      (node (ref "U3") (pin "5") (pinfunction "I_5") (pintype "input"))
    )
    (net (code "23") (name "/ROTA_FILT") (class "Default")
      (node (ref "U1") (pin "36") (pinfunction "GPIO24_36") (pintype "bidirectional"))
      (node (ref "U3") (pin "4") (pinfunction "O_4") (pintype "output"))
    )
    (net (code "24") (name "/ROTB") (class "Default")
      (node (ref "C22") (pin "2") (pinfunction "2_2") (pintype "passive"))
      (node (ref "R52") (pin "1") (pinfunction "1_1") (pintype "passive"))
      (node (ref "S1") (pin "B") (pinfunction "B_B") (pintype "bidirectional"))
      (node (ref "U3") (pin "11") (pinfunction "I_11") (pintype "input"))
    )
    (net (code "25") (name "/ROTB_FILT") (class "Default")
      (node (ref "U1") (pin "15") (pinfunction "GPIO12_15") (pintype "bidirectional"))
      (node (ref "U3") (pin "8") (pinfunction "O_8") (pintype "output"))
    )
    (net (code "26") (name "/ROTPUSH") (class "Default")
      (node (ref "C24") (pin "2") (pinfunction "2_2") (pintype "passive"))
      (node (ref "R54") (pin "1") (pinfunction "1_1") (pintype "passive"))
      (node (ref "S1") (pin "SW+") (pinfunction "SW+_SW+") (pintype "bidirectional"))
      (node (ref "U3") (pin "1") (pinfunction "I_1") (pintype "input"))
    )
    (net (code "27") (name "/RPUSH_FILT") (class "Default")
      (node (ref "U1") (pin "8") (pinfunction "GPIO6_8") (pintype "bidirectional"))
      (node (ref "U3") (pin "12") (pinfunction "O_12") (pintype "output"))
    )
    (net (code "28") (name "/RST") (class "Default")
      (node (ref "J6") (pin "5") (pinfunction "RST_5") (pintype "bidirectional"))
      (node (ref "R21") (pin "2") (pinfunction "2_2") (pintype "passive"))
    )
    (net (code "29") (name "/RUN") (class "Default")
      (node (ref "JP1") (pin "10") (pinfunction "10_10") (pintype "passive"))
      (node (ref "RUN") (pin "TP") (pinfunction "TP_TP") (pintype "input"))
      (node (ref "U1") (pin "26") (pinfunction "RUN_26") (pintype "bidirectional"))
    )
    (net (code "30") (name "/RX") (class "Default")
      (node (ref "U1") (pin "3") (pinfunction "GPIO1_3") (pintype "bidirectional"))
    )
    (net (code "31") (name "/SCK") (class "Default")
      (node (ref "R14") (pin "1") (pinfunction "1_1") (pintype "passive"))
      (node (ref "U1") (pin "29") (pinfunction "GPIO18_29") (pintype "bidirectional"))
    )
    (net (code "32") (name "/SEL") (class "Default")
      (node (ref "K1") (pin "3") (pinfunction "P$3_3") (pintype "bidirectional"))
      (node (ref "SEL") (pin "TP") (pinfunction "TP_TP") (pintype "input"))
      (node (ref "U1") (pin "37") (pinfunction "GPIO25_37") (pintype "bidirectional"))
    )
    (net (code "33") (name "/SS") (class "Default")
      (node (ref "R29") (pin "1") (pinfunction "1_1") (pintype "passive"))
      (node (ref "U1") (pin "28") (pinfunction "GPIO17_28") (pintype "bidirectional"))
    )
    (net (code "34") (name "/SWCLK") (class "Default")
      (node (ref "JP1") (pin "4") (pinfunction "4_4") (pintype "passive"))
      (node (ref "SWCLK") (pin "TP") (pinfunction "TP_TP") (pintype "input"))
      (node (ref "U1") (pin "24") (pinfunction "SWCLK_24") (pintype "bidirectional"))
    )
    (net (code "35") (name "/SWDIO") (class "Default")
      (node (ref "JP1") (pin "2") (pinfunction "2_2") (pintype "passive"))
      (node (ref "SWDIO") (pin "TP") (pinfunction "TP_TP") (pintype "input"))
      (node (ref "U1") (pin "25") (pinfunction "SWDIO_25") (pintype "bidirectional"))
    )
    (net (code "36") (name "/SWO") (class "Default")
      (node (ref "JP1") (pin "6") (pinfunction "6_6") (pintype "passive"))
    )
    (net (code "37") (name "/TDI") (class "Default")
      (node (ref "JP1") (pin "8") (pinfunction "8_8") (pintype "passive"))
    )
    (net (code "38") (name "/TX") (class "Default")
      (node (ref "U1") (pin "2") (pinfunction "GPIO0_2") (pintype "bidirectional"))
    )
    (net (code "39") (name "/USB_D+") (class "Default")
      (node (ref "D4") (pin "2") (pinfunction "CATHODE_2_2") (pintype "bidirectional"))
      (node (ref "J1") (pin "6") (pinfunction "D+_6") (pintype "passive"))
      (node (ref "J1") (pin "7") (pinfunction "D+_7") (pintype "passive"))
      (node (ref "USB-D+") (pin "TP") (pinfunction "TP_TP") (pintype "input"))
      (node (ref "USB_D+") (pin "2") (pinfunction "2_2") (pintype "passive"))
    )
    (net (code "40") (name "/USB_D-") (class "Default")
      (node (ref "D4") (pin "1") (pinfunction "CATHODE_1_1") (pintype "bidirectional"))
      (node (ref "J1") (pin "5") (pinfunction "D-_5") (pintype "passive"))
      (node (ref "J1") (pin "8") (pinfunction "D-_8") (pintype "passive"))
      (node (ref "USB-D-") (pin "TP") (pinfunction "TP_TP") (pintype "input"))
      (node (ref "USB_D-") (pin "2") (pinfunction "2_2") (pintype "passive"))
    )
    (net (code "41") (name "/USB_DM") (class "Default")
      (node (ref "R63") (pin "2") (pinfunction "2_2") (pintype "passive"))
      (node (ref "U1") (pin "46") (pinfunction "USB_DM_46") (pintype "bidirectional"))
    )
    (net (code "42") (name "/USB_DP") (class "Default")
      (node (ref "R38") (pin "2") (pinfunction "2_2") (pintype "passive"))
      (node (ref "U1") (pin "47") (pinfunction "USB_DP_47") (pintype "bidirectional"))
    )
    (net (code "43") (name "/VBUS_SENSE") (class "Default")
      (node (ref "C58") (pin "2") (pinfunction "2_2") (pintype "passive"))
      (node (ref "D7") (pin "3") (pinfunction "AC_3") (pintype "passive"))
      (node (ref "R50") (pin "1") (pinfunction "1_1") (pintype "passive"))
      (node (ref "R51") (pin "2") (pinfunction "2_2") (pintype "passive"))
      (node (ref "U1") (pin "38") (pinfunction "GPIO26_/_ADC0_38") (pintype "bidirectional"))
      (node (ref "VBUS_SENSE") (pin "TP") (pinfunction "TP_TP") (pintype "input"))
    )
    (net (code "44") (name "/VOSEN") (class "Default")
      (node (ref "C13") (pin "2") (pinfunction "2_2") (pintype "passive"))
      (node (ref "D2") (pin "3") (pinfunction "AC_3") (pintype "passive"))
      (node (ref "R36") (pin "1") (pinfunction "1_1") (pintype "passive"))
      (node (ref "R37") (pin "2") (pinfunction "2_2") (pintype "passive"))
      (node (ref "U1") (pin "40") (pinfunction "GPIO28_/_ADC2_40") (pintype "bidirectional"))
      (node (ref "VOSEN") (pin "TP") (pinfunction "TP_TP") (pintype "input"))
    )
    (net (code "45") (name "/VO_TPS") (class "Default")
      (node (ref "C19") (pin "2") (pinfunction "2_2") (pintype "passive"))
      (node (ref "C34") (pin "2") (pinfunction "2_2") (pintype "passive"))
      (node (ref "C39") (pin "1") (pinfunction "1_1") (pintype "passive"))
      (node (ref "C40") (pin "1") (pinfunction "1_1") (pintype "passive"))
      (node (ref "C41") (pin "1") (pinfunction "1_1") (pintype "passive"))
      (node (ref "C42") (pin "1") (pinfunction "1_1") (pintype "passive"))
      (node (ref "C43") (pin "1") (pinfunction "1_1") (pintype "passive"))
      (node (ref "L2") (pin "2") (pinfunction "2_2") (pintype "passive"))
      (node (ref "R11") (pin "2") (pinfunction "2_2") (pintype "passive"))
      (node (ref "R12") (pin "1") (pinfunction "1_1") (pintype "passive"))
      (node (ref "U4") (pin "5") (pinfunction "RS+_5") (pintype "power_in"))
    )
    (net (code "46") (name "1v1") (class "Default")
      (node (ref "C32") (pin "2") (pinfunction "2_2") (pintype "passive"))
      (node (ref "C33") (pin "2") (pinfunction "2_2") (pintype "passive"))
      (node (ref "C46") (pin "1") (pinfunction "1_1") (pintype "passive"))
      (node (ref "U1") (pin "23") (pinfunction "DVDD_1_23") (pintype "bidirectional"))
      (node (ref "U1") (pin "45") (pinfunction "VREG_VOUT_45") (pintype "bidirectional"))
      (node (ref "U1") (pin "50") (pinfunction "DVDD_2_50") (pintype "bidirectional"))
    )
    (net (code "47") (name "3V3MCU") (class "Default")
      (node (ref "3V3MCU") (pin "TP") (pinfunction "TP_TP") (pintype "input"))
      (node (ref "C12") (pin "2") (pinfunction "2_2") (pintype "passive"))
      (node (ref "C15") (pin "1") (pinfunction "1_1") (pintype "passive"))
      (node (ref "C16") (pin "2") (pinfunction "2_2") (pintype "passive"))
      (node (ref "C2") (pin "2") (pinfunction "2_2") (pintype "passive"))
      (node (ref "C20") (pin "2") (pinfunction "2_2") (pintype "passive"))
      (node (ref "C25") (pin "2") (pinfunction "2_2") (pintype "passive"))
      (node (ref "C26") (pin "1") (pinfunction "1_1") (pintype "passive"))
      (node (ref "C3") (pin "2") (pinfunction "2_2") (pintype "passive"))
      (node (ref "C31") (pin "2") (pinfunction "2_2") (pintype "passive"))
      (node (ref "C44") (pin "2") (pinfunction "2_2") (pintype "passive"))
      (node (ref "C45") (pin "1") (pinfunction "1_1") (pintype "passive"))
      (node (ref "C5") (pin "2") (pinfunction "2_2") (pintype "passive"))
      (node (ref "C50") (pin "2") (pinfunction "2_2") (pintype "passive"))
      (node (ref "C51") (pin "2") (pinfunction "2_2") (pintype "passive"))
      (node (ref "C52") (pin "2") (pinfunction "2_2") (pintype "passive"))
      (node (ref "C53") (pin "2") (pinfunction "2_2") (pintype "passive"))
      (node (ref "C57") (pin "1") (pinfunction "1_1") (pintype "passive"))
      (node (ref "C6") (pin "2") (pinfunction "2_2") (pintype "passive"))
      (node (ref "C60") (pin "2") (pinfunction "2_2") (pintype "passive"))
      (node (ref "C62") (pin "2") (pinfunction "2_2") (pintype "passive"))
      (node (ref "C7") (pin "2") (pinfunction "2_2") (pintype "passive"))
      (node (ref "C8") (pin "2") (pinfunction "2_2") (pintype "passive"))
      (node (ref "D2") (pin "2") (pinfunction "C_2") (pintype "passive"))
      (node (ref "D3") (pin "2") (pinfunction "C_2") (pintype "passive"))
      (node (ref "D7") (pin "2") (pinfunction "C_2") (pintype "passive"))
      (node (ref "DZ1") (pin "1") (pinfunction "K_1") (pintype "bidirectional"))
      (node (ref "J6") (pin "2") (pinfunction "VCC_2") (pintype "bidirectional"))
      (node (ref "JP1") (pin "1") (pinfunction "1_1") (pintype "passive"))
      (node (ref "K1") (pin "4") (pinfunction "P$4_4") (pintype "bidirectional"))
      (node (ref "L1") (pin "2") (pinfunction "2_2") (pintype "bidirectional"))
      (node (ref "LS1") (pin "1") (pinfunction "+_1") (pintype "bidirectional"))
      (node (ref "R13") (pin "2") (pinfunction "2_2") (pintype "passive"))
      (node (ref "R15") (pin "1") (pinfunction "1_1") (pintype "passive"))
      (node (ref "R19") (pin "2") (pinfunction "2_2") (pintype "passive"))
      (node (ref "R35") (pin "1") (pinfunction "1_1") (pintype "passive"))
      (node (ref "R40") (pin "2") (pinfunction "2_2") (pintype "passive"))
      (node (ref "R52") (pin "2") (pinfunction "2_2") (pintype "passive"))
      (node (ref "R53") (pin "2") (pinfunction "2_2") (pintype "passive"))
      (node (ref "R54") (pin "2") (pinfunction "2_2") (pintype "passive"))
      (node (ref "R57") (pin "2") (pinfunction "2_2") (pintype "passive"))
      (node (ref "R64") (pin "2") (pinfunction "2_2") (pintype "passive"))
      (node (ref "R66") (pin "1") (pinfunction "1_1") (pintype "passive"))
      (node (ref "R67") (pin "2") (pinfunction "2_2") (pintype "passive"))
      (node (ref "U1") (pin "1") (pinfunction "IOVDD_1_1") (pintype "bidirectional"))
      (node (ref "U1") (pin "10") (pinfunction "IOVDD_2_10") (pintype "bidirectional"))
      (node (ref "U1") (pin "22") (pinfunction "IOVDD_3_22") (pintype "bidirectional"))
      (node (ref "U1") (pin "33") (pinfunction "IOVDD_4_33") (pintype "bidirectional"))
      (node (ref "U1") (pin "42") (pinfunction "IOVDD_5_42") (pintype "bidirectional"))
      (node (ref "U1") (pin "44") (pinfunction "VREG_VIN_44") (pintype "bidirectional"))
      (node (ref "U1") (pin "48") (pinfunction "USB_VDD_48") (pintype "bidirectional"))
      (node (ref "U1") (pin "49") (pinfunction "IOVDD_6_49") (pintype "bidirectional"))
      (node (ref "U2") (pin "3") (pinfunction "VDD_3") (pintype "bidirectional"))
      (node (ref "U3") (pin "14") (pinfunction "VCC_14") (pintype "power_in"))
      (node (ref "U5") (pin "8") (pinfunction "VCC_8") (pintype "bidirectional"))
      (node (ref "U6") (pin "14") (pinfunction "VCC_14") (pintype "power_in"))
      (node (ref "U7") (pin "1") (pinfunction "VCC_1") (pintype "bidirectional"))
      (node (ref "U9") (pin "1") (pinfunction "VCC_1") (pintype "power_in"))
    )
    (net (code "48") (name "EN_DCDC") (class "Default")
      (node (ref "R27") (pin "2") (pinfunction "2_2") (pintype "passive"))
      (node (ref "R31") (pin "1") (pinfunction "1_1") (pintype "passive"))
      (node (ref "U1") (pin "4") (pinfunction "GPIO2_4") (pintype "bidirectional"))
    )
    (net (code "49") (name "GND") (class "Default")
      (node (ref "C10") (pin "1") (pinfunction "1_1") (pintype "passive"))
      (node (ref "C11") (pin "1") (pinfunction "1_1") (pintype "passive"))
      (node (ref "C12") (pin "1") (pinfunction "1_1") (pintype "passive"))
      (node (ref "C13") (pin "1") (pinfunction "1_1") (pintype "passive"))
      (node (ref "C14") (pin "1") (pinfunction "1_1") (pintype "passive"))
      (node (ref "C15") (pin "2") (pinfunction "2_2") (pintype "passive"))
      (node (ref "C16") (pin "1") (pinfunction "1_1") (pintype "passive"))
      (node (ref "C17") (pin "2") (pinfunction "2_2") (pintype "passive"))
      (node (ref "C18") (pin "2") (pinfunction "2_2") (pintype "passive"))
      (node (ref "C2") (pin "1") (pinfunction "1_1") (pintype "passive"))
      (node (ref "C20") (pin "1") (pinfunction "1_1") (pintype "passive"))
      (node (ref "C21") (pin "2") (pinfunction "2_2") (pintype "passive"))
      (node (ref "C22") (pin "1") (pinfunction "1_1") (pintype "passive"))
      (node (ref "C23") (pin "1") (pinfunction "1_1") (pintype "passive"))
      (node (ref "C24") (pin "1") (pinfunction "1_1") (pintype "passive"))
      (node (ref "C25") (pin "1") (pinfunction "1_1") (pintype "passive"))
      (node (ref "C26") (pin "2") (pinfunction "2_2") (pintype "passive"))
      (node (ref "C27") (pin "1") (pinfunction "1_1") (pintype "passive"))
      (node (ref "C28") (pin "1") (pinfunction "1_1") (pintype "passive"))
      (node (ref "C3") (pin "1") (pinfunction "1_1") (pintype "passive"))
      (node (ref "C30") (pin "1") (pinfunction "1_1") (pintype "passive"))
      (node (ref "C31") (pin "1") (pinfunction "1_1") (pintype "passive"))
      (node (ref "C32") (pin "1") (pinfunction "1_1") (pintype "passive"))
      (node (ref "C33") (pin "1") (pinfunction "1_1") (pintype "passive"))
      (node (ref "C34") (pin "1") (pinfunction "1_1") (pintype "passive"))
      (node (ref "C35") (pin "2") (pinfunction "2_2") (pintype "passive"))
      (node (ref "C36") (pin "1") (pinfunction "1_1") (pintype "passive"))
      (node (ref "C38") (pin "1") (pinfunction "1_1") (pintype "passive"))
      (node (ref "C39") (pin "2") (pinfunction "2_2") (pintype "passive"))
      (node (ref "C40") (pin "2") (pinfunction "2_2") (pintype "passive"))
      (node (ref "C41") (pin "2") (pinfunction "2_2") (pintype "passive"))
      (node (ref "C42") (pin "2") (pinfunction "2_2") (pintype "passive"))
      (node (ref "C44") (pin "1") (pinfunction "1_1") (pintype "passive"))
      (node (ref "C45") (pin "2") (pinfunction "2_2") (pintype "passive"))
      (node (ref "C46") (pin "2") (pinfunction "2_2") (pintype "passive"))
      (node (ref "C47") (pin "1") (pinfunction "1_1") (pintype "passive"))
      (node (ref "C48") (pin "1") (pinfunction "1_1") (pintype "passive"))
      (node (ref "C49") (pin "1") (pinfunction "1_1") (pintype "passive"))
      (node (ref "C5") (pin "1") (pinfunction "1_1") (pintype "passive"))
      (node (ref "C50") (pin "1") (pinfunction "1_1") (pintype "passive"))
      (node (ref "C51") (pin "1") (pinfunction "1_1") (pintype "passive"))
      (node (ref "C53") (pin "1") (pinfunction "1_1") (pintype "passive"))
      (node (ref "C54") (pin "1") (pinfunction "1_1") (pintype "passive"))
      (node (ref "C57") (pin "2") (pinfunction "2_2") (pintype "passive"))
      (node (ref "C58") (pin "1") (pinfunction "1_1") (pintype "passive"))
      (node (ref "C59") (pin "1") (pinfunction "1_1") (pintype "passive"))
      (node (ref "C6") (pin "1") (pinfunction "1_1") (pintype "passive"))
      (node (ref "C60") (pin "1") (pinfunction "1_1") (pintype "passive"))
      (node (ref "C61") (pin "1") (pinfunction "1_1") (pintype "passive"))
      (node (ref "C62") (pin "1") (pinfunction "1_1") (pintype "passive"))
      (node (ref "C63") (pin "1") (pinfunction "1_1") (pintype "passive"))
      (node (ref "C64") (pin "1") (pinfunction "1_1") (pintype "passive"))
      (node (ref "C65") (pin "1") (pinfunction "1_1") (pintype "passive"))
      (node (ref "C66") (pin "1") (pinfunction "1_1") (pintype "passive"))
      (node (ref "C7") (pin "1") (pinfunction "1_1") (pintype "passive"))
      (node (ref "C8") (pin "1") (pinfunction "1_1") (pintype "passive"))
      (node (ref "C9") (pin "2") (pinfunction "2_2") (pintype "passive"))
      (node (ref "D2") (pin "1") (pinfunction "A_1") (pintype "passive"))
      (node (ref "D6") (pin "1") (pinfunction "A_1") (pintype "bidirectional"))
      (node (ref "D7") (pin "1") (pinfunction "A_1") (pintype "passive"))
      (node (ref "D8") (pin "2") (pinfunction "A_2") (pintype "bidirectional"))
      (node (ref "DZ1") (pin "2") (pinfunction "A_2") (pintype "bidirectional"))
      (node (ref "GND") (pin "TP") (pinfunction "TP_TP") (pintype "input"))
      (node (ref "J6") (pin "1") (pinfunction "GND_1") (pintype "bidirectional"))
      (node (ref "JP1") (pin "3") (pinfunction "3_3") (pintype "passive"))
      (node (ref "JP1") (pin "5") (pinfunction "5_5") (pintype "passive"))
      (node (ref "JP1") (pin "7") (pinfunction "7_7") (pintype "passive"))
      (node (ref "JP1") (pin "9") (pinfunction "9_9") (pintype "passive"))
      (node (ref "K1") (pin "8") (pinfunction "P$7_8") (pintype "bidirectional"))
      (node (ref "K1") (pin "9") (pinfunction "P$8_9") (pintype "bidirectional"))
      (node (ref "OP1") (pin "3") (pinfunction "EMIT_3") (pintype "passive"))
      (node (ref "Q2") (pin "2") (pinfunction "S_2") (pintype "passive"))
      (node (ref "Q5") (pin "2") (pinfunction "S_2") (pintype "passive"))
      (node (ref "Q9") (pin "2") (pinfunction "S_2") (pintype "passive"))
      (node (ref "R16") (pin "2") (pinfunction "2_2") (pintype "passive"))
      (node (ref "R18") (pin "1") (pinfunction "1_1") (pintype "passive"))
      (node (ref "R22") (pin "2") (pinfunction "2_2") (pintype "passive"))
      (node (ref "R32") (pin "2") (pinfunction "2_2") (pintype "passive"))
      (node (ref "R36") (pin "2") (pinfunction "2_2") (pintype "passive"))
      (node (ref "R42") (pin "1") (pinfunction "1_1") (pintype "passive"))
      (node (ref "R43") (pin "1") (pinfunction "1_1") (pintype "passive"))
      (node (ref "R44") (pin "1") (pinfunction "1_1") (pintype "passive"))
      (node (ref "R45") (pin "1") (pinfunction "1_1") (pintype "passive"))
      (node (ref "R49") (pin "1") (pinfunction "1_1") (pintype "passive"))
      (node (ref "R50") (pin "2") (pinfunction "2_2") (pintype "passive"))
      (node (ref "R59") (pin "1") (pinfunction "1_1") (pintype "passive"))
      (node (ref "RSENSE") (pin "2") (pinfunction "2_2") (pintype "passive"))
      (node (ref "S1") (pin "C") (pinfunction "C_C") (pintype "bidirectional"))
      (node (ref "S1") (pin "SW-") (pinfunction "SW-_SW-") (pintype "bidirectional"))
      (node (ref "S2") (pin "2") (pinfunction "2_2") (pintype "passive"))
      (node (ref "U1") (pin "19") (pinfunction "TESTEN_19") (pintype "bidirectional"))
      (node (ref "U1") (pin "57") (pinfunction "GND_57") (pintype "bidirectional"))
      (node (ref "U11") (pin "4") (pinfunction "GND_4") (pintype "bidirectional"))
      (node (ref "U12") (pin "7") (pinfunction "GND_7") (pintype "bidirectional"))
      (node (ref "U12") (pin "9") (pinfunction "EP_9") (pintype "bidirectional"))
      (node (ref "U2") (pin "2") (pinfunction "VSS_2") (pintype "bidirectional"))
      (node (ref "U2") (pin "6") (pinfunction "AO_6") (pintype "bidirectional"))
      (node (ref "U3") (pin "7") (pinfunction "GND_7") (pintype "power_in"))
      (node (ref "U4") (pin "1") (pinfunction "GND_1") (pintype "passive"))
      (node (ref "U4") (pin "2") (pinfunction "GND_2_2") (pintype "passive"))
      (node (ref "U5") (pin "4") (pinfunction "GND_4") (pintype "bidirectional"))
      (node (ref "U6") (pin "7") (pinfunction "GND_7") (pintype "power_in"))
      (node (ref "U7") (pin "10") (pinfunction "A1_10") (pintype "bidirectional"))
      (node (ref "U7") (pin "16") (pinfunction "GND_16") (pintype "bidirectional"))
      (node (ref "U7") (pin "7") (pinfunction "A2_7") (pintype "bidirectional"))
      (node (ref "U7") (pin "8") (pinfunction "~{G}_8") (pintype "bidirectional"))
      (node (ref "U7") (pin "9") (pinfunction "A0_9") (pintype "bidirectional"))
      (node (ref "U8") (pin "2") (pinfunction "ANODE_1_2") (pintype "bidirectional"))
      (node (ref "X1") (pin "2") (pinfunction "GND_1_2") (pintype "bidirectional"))
      (node (ref "X1") (pin "4") (pinfunction "GND_2_4") (pintype "bidirectional"))
    )
    (net (code "50") (name "GND_IN") (class "Default")
      (node (ref "C55") (pin "2") (pinfunction "2_2") (pintype "passive"))
      (node (ref "C56") (pin "2") (pinfunction "2_2") (pintype "passive"))
      (node (ref "D1") (pin "A") (pinfunction "A_A") (pintype "passive"))
      (node (ref "D4") (pin "3") (pinfunction "COMMON_CATHODE_3") (pintype "bidirectional"))
      (node (ref "GND_IN") (pin "TP") (pinfunction "TP_TP") (pintype "input"))
      (node (ref "J1") (pin "1") (pinfunction "GND_1") (pintype "power_in"))
      (node (ref "J1") (pin "12") (pinfunction "GND_12") (pintype "power_in"))
      (node (ref "J1") (pin "S1") (pinfunction "SHIELD_S1") (pintype "passive"))
      (node (ref "J1") (pin "S2") (pinfunction "SHIELD_S2") (pintype "passive"))
      (node (ref "J1") (pin "S3") (pinfunction "SHIELD_S3") (pintype "passive"))
      (node (ref "J1") (pin "S4") (pinfunction "SHIELD_S4") (pintype "passive"))
      (node (ref "J1") (pin "S5") (pinfunction "SHIELD_S5") (pintype "passive"))
      (node (ref "J1") (pin "S6") (pinfunction "SHIELD_S6") (pintype "passive"))
      (node (ref "R34") (pin "1") (pinfunction "1_1") (pintype "passive"))
      (node (ref "R55") (pin "1") (pinfunction "1_1") (pintype "passive"))
      (node (ref "R56") (pin "1") (pinfunction "1_1") (pintype "passive"))
      (node (ref "RSENSE") (pin "1") (pinfunction "1_1") (pintype "passive"))
      (node (ref "U10") (pin "5") (pinfunction "GND_5") (pintype "bidirectional"))
      (node (ref "U9") (pin "2") (pinfunction "GND_2_2") (pintype "power_in"))
      (node (ref "U9") (pin "3") (pinfunction "GND_3") (pintype "power_in"))
    )
    (net (code "51") (name "IN+") (class "Default")
      (node (ref "C36") (pin "2") (pinfunction "2_2") (pintype "passive"))
      (node (ref "C56") (pin "1") (pinfunction "1_1") (pintype "passive"))
      (node (ref "D1") (pin "C") (pinfunction "K_C") (pintype "passive"))
      (node (ref "IN+") (pin "TP") (pinfunction "TP_TP") (pintype "input"))
      (node (ref "J1") (pin "11") (pinfunction "VBUS_11") (pintype "power_in"))
      (node (ref "J1") (pin "2") (pinfunction "VBUS_2") (pintype "power_in"))
      (node (ref "PTC1") (pin "2") (pinfunction "2_2") (pintype "passive"))
      (node (ref "R47") (pin "1") (pinfunction "1_1") (pintype "passive"))
      (node (ref "R51") (pin "1") (pinfunction "1_1") (pintype "passive"))
      (node (ref "R62") (pin "2") (pinfunction "2_2") (pintype "passive"))
    )
    (net (code "52") (name "IN_OVC") (class "Default")
      (node (ref "Q5") (pin "1") (pinfunction "G_1") (pintype "passive"))
      (node (ref "R48") (pin "2") (pinfunction "2_2") (pintype "passive"))
      (node (ref "R49") (pin "2") (pinfunction "2_2") (pintype "passive"))
      (node (ref "U6") (pin "13") (pinfunction "I_13") (pintype "input"))
    )
    (net (code "53") (name "ISENSE") (class "Default")
      (node (ref "ISENSE") (pin "TP") (pinfunction "TP_TP") (pintype "input"))
      (node (ref "U1") (pin "39") (pinfunction "GPIO27_/_ADC1_39") (pintype "bidirectional"))
      (node (ref "U4") (pin "3") (pinfunction "OUT_3") (pintype "output"))
    )
    (net (code "54") (name "Net-(BZ1-+)") (class "Default")
      (node (ref "BZ1") (pin "1") (pinfunction "+_1") (pintype "passive"))
      (node (ref "C27") (pin "2") (pinfunction "2_2") (pintype "passive"))
      (node (ref "L7") (pin "2") (pinfunction "2_2") (pintype "passive"))
      (node (ref "R61") (pin "2") (pinfunction "2_2") (pintype "passive"))
    )
    (net (code "55") (name "Net-(BZ1--)") (class "Default")
      (node (ref "BZ1") (pin "2") (pinfunction "-_2") (pintype "passive"))
      (node (ref "D3") (pin "3") (pinfunction "AC_3") (pintype "passive"))
      (node (ref "LS1") (pin "2") (pinfunction "-_2") (pintype "bidirectional"))
      (node (ref "Q9") (pin "3") (pinfunction "D_3") (pintype "passive"))
      (node (ref "R61") (pin "1") (pinfunction "1_1") (pintype "passive"))
    )
    (net (code "56") (name "Net-(C10-Pad2)") (class "Default")
      (node (ref "C10") (pin "2") (pinfunction "2_2") (pintype "passive"))
      (node (ref "R13") (pin "1") (pinfunction "1_1") (pintype "passive"))
      (node (ref "R65") (pin "2") (pinfunction "2_2") (pintype "passive"))
      (node (ref "S2") (pin "4") (pinfunction "4_4") (pintype "passive"))
    )
    (net (code "57") (name "Net-(C37-Pad1)") (class "Default")
      (node (ref "C37") (pin "1") (pinfunction "1_1") (pintype "passive"))
      (node (ref "R44") (pin "2") (pinfunction "2_2") (pintype "passive"))
    )
    (net (code "58") (name "Net-(C52-Pad1)") (class "Default")
      (node (ref "C52") (pin "1") (pinfunction "1_1") (pintype "passive"))
      (node (ref "FB_ADJ") (pin "1") (pinfunction "1_1") (pintype "passive"))
      (node (ref "R15") (pin "2") (pinfunction "2_2") (pintype "passive"))
      (node (ref "R16") (pin "1") (pinfunction "1_1") (pintype "passive"))
    )
    (net (code "59") (name "Net-(D5-A)") (class "Default")
      (node (ref "D5") (pin "2") (pinfunction "A_2") (pintype "bidirectional"))
      (node (ref "OP1") (pin "1") (pinfunction "A_1") (pintype "passive"))
    )
    (net (code "60") (name "Net-(J6-DC)") (class "Default")
      (node (ref "J6") (pin "6") (pinfunction "DC_6") (pintype "bidirectional"))
      (node (ref "R24") (pin "2") (pinfunction "2_2") (pintype "passive"))
    )
    (net (code "61") (name "Net-(L3-Pad2)") (class "Default")
      (node (ref "L3") (pin "2") (pinfunction "2_2") (pintype "passive"))
      (node (ref "R26") (pin "1") (pinfunction "1_1") (pintype "passive"))
    )
    (net (code "62") (name "Net-(L4-Pad2)") (class "Default")
      (node (ref "L4") (pin "2") (pinfunction "2_2") (pintype "passive"))
      (node (ref "R22") (pin "1") (pinfunction "1_1") (pintype "passive"))
    )
    (net (code "63") (name "Net-(LED1-C)") (class "Default")
      (node (ref "LED1") (pin "K") (pinfunction "C_K") (pintype "passive"))
      (node (ref "Q2") (pin "3") (pinfunction "D_3") (pintype "passive"))
    )
    (net (code "64") (name "Net-(LED1-PadA)") (class "Default")
      (node (ref "LED1") (pin "A") (pinfunction "A_A") (pintype "passive"))
      (node (ref "R35") (pin "2") (pinfunction "2_2") (pintype "passive"))
    )
    (net (code "65") (name "Net-(Q2-G)") (class "Default")
      (node (ref "Q2") (pin "1") (pinfunction "G_1") (pintype "passive"))
      (node (ref "R31") (pin "2") (pinfunction "2_2") (pintype "passive"))
    )
    (net (code "66") (name "Net-(Q4-D)") (class "Default")
      (node (ref "Q4") (pin "3") (pinfunction "D_3") (pintype "passive"))
      (node (ref "R41") (pin "1") (pinfunction "1_1") (pintype "passive"))
    )
    (net (code "67") (name "Net-(Q9-G)") (class "Default")
      (node (ref "Q9") (pin "1") (pinfunction "G_1") (pintype "passive"))
      (node (ref "R28") (pin "2") (pinfunction "2_2") (pintype "passive"))
      (node (ref "R32") (pin "1") (pinfunction "1_1") (pintype "passive"))
    )
    (net (code "68") (name "Net-(R38-Pad1)") (class "Default")
      (node (ref "R38") (pin "1") (pinfunction "1_1") (pintype "passive"))
      (node (ref "USB_D+") (pin "1") (pinfunction "1_1") (pintype "passive"))
    )
    (net (code "69") (name "Net-(R63-Pad1)") (class "Default")
      (node (ref "R63") (pin "1") (pinfunction "1_1") (pintype "passive"))
      (node (ref "USB_D-") (pin "1") (pinfunction "1_1") (pintype "passive"))
    )
    (net (code "70") (name "Net-(U2-SCL)") (class "Default")
      (node (ref "R58") (pin "2") (pinfunction "2_2") (pintype "passive"))
      (node (ref "U2") (pin "5") (pinfunction "SCL_5") (pintype "bidirectional"))
    )
    (net (code "71") (name "Net-(U2-SDA)") (class "Default")
      (node (ref "R60") (pin "2") (pinfunction "2_2") (pintype "passive"))
      (node (ref "U2") (pin "4") (pinfunction "SDA_4") (pintype "bidirectional"))
    )
    (net (code "72") (name "Net-(U3A-I)") (class "Default")
      (node (ref "C49") (pin "2") (pinfunction "2_2") (pintype "passive"))
      (node (ref "R25") (pin "2") (pinfunction "2_2") (pintype "passive"))
      (node (ref "U3") (pin "13") (pinfunction "I_13") (pintype "input"))
    )
    (net (code "73") (name "Net-(U3B-O)") (class "Default")
      (node (ref "R2") (pin "1") (pinfunction "1_1") (pintype "passive"))
      (node (ref "U3") (pin "10") (pinfunction "O_10") (pintype "output"))
    )
    (net (code "74") (name "Net-(U3C-I)") (class "Default")
      (node (ref "C47") (pin "2") (pinfunction "2_2") (pintype "passive"))
      (node (ref "R2") (pin "2") (pinfunction "2_2") (pintype "passive"))
      (node (ref "U3") (pin "9") (pinfunction "I_9") (pintype "input"))
    )
    (net (code "75") (name "Net-(U3D-O)") (class "Default")
      (node (ref "R25") (pin "1") (pinfunction "1_1") (pintype "passive"))
      (node (ref "U3") (pin "2") (pinfunction "O_2") (pintype "output"))
    )
    (net (code "76") (name "Net-(U3E-I)") (class "Default")
      (node (ref "C48") (pin "2") (pinfunction "2_2") (pintype "passive"))
      (node (ref "R20") (pin "2") (pinfunction "2_2") (pintype "passive"))
      (node (ref "U3") (pin "3") (pinfunction "I_3") (pintype "input"))
    )
    (net (code "77") (name "Net-(U3F-O)") (class "Default")
      (node (ref "R20") (pin "1") (pinfunction "1_1") (pintype "passive"))
      (node (ref "U3") (pin "6") (pinfunction "O_6") (pintype "output"))
    )
    (net (code "78") (name "Net-(U4-RS-)") (class "Default")
      (node (ref "C43") (pin "2") (pinfunction "2_2") (pintype "passive"))
      (node (ref "R1") (pin "1") (pinfunction "1_1") (pintype "passive"))
      (node (ref "U4") (pin "4") (pinfunction "RS-_4") (pintype "input"))
    )
    (net (code "79") (name "Net-(U6A-O)") (class "Default")
      (node (ref "R39") (pin "1") (pinfunction "1_1") (pintype "passive"))
      (node (ref "U6") (pin "12") (pinfunction "O_12") (pintype "output"))
    )
    (net (code "80") (name "Net-(U6B-I)") (class "Default")
      (node (ref "C54") (pin "2") (pinfunction "2_2") (pintype "passive"))
      (node (ref "R39") (pin "2") (pinfunction "2_2") (pintype "passive"))
      (node (ref "U6") (pin "11") (pinfunction "I_11") (pintype "input"))
    )
    (net (code "81") (name "Net-(U6C-I)") (class "Default")
      (node (ref "C14") (pin "2") (pinfunction "2_2") (pintype "passive"))
      (node (ref "R33") (pin "2") (pinfunction "2_2") (pintype "passive"))
      (node (ref "U6") (pin "9") (pinfunction "I_9") (pintype "input"))
    )
    (net (code "82") (name "Net-(U6D-O)") (class "Default")
      (node (ref "R23") (pin "1") (pinfunction "1_1") (pintype "passive"))
      (node (ref "U6") (pin "2") (pinfunction "O_2") (pintype "output"))
    )
    (net (code "83") (name "Net-(U6E-I)") (class "Default")
      (node (ref "C11") (pin "2") (pinfunction "2_2") (pintype "passive"))
      (node (ref "R23") (pin "2") (pinfunction "2_2") (pintype "passive"))
      (node (ref "U6") (pin "3") (pinfunction "I_3") (pintype "input"))
    )
    (net (code "84") (name "Net-(U6F-O)") (class "Default")
      (node (ref "R33") (pin "1") (pinfunction "1_1") (pintype "passive"))
      (node (ref "U6") (pin "6") (pinfunction "O_6") (pintype "output"))
    )
    (net (code "85") (name "Net-(U7-DRAIN0)") (class "Default")
      (node (ref "R6") (pin "1") (pinfunction "1_1") (pintype "passive"))
      (node (ref "U7") (pin "3") (pinfunction "DRAIN0_3") (pintype "bidirectional"))
    )
    (net (code "86") (name "Net-(U7-DRAIN1)") (class "Default")
      (node (ref "R5") (pin "1") (pinfunction "1_1") (pintype "passive"))
      (node (ref "U7") (pin "4") (pinfunction "DRAIN1_4") (pintype "bidirectional"))
    )
    (net (code "87") (name "Net-(U7-DRAIN2)") (class "Default")
      (node (ref "R4") (pin "1") (pinfunction "1_1") (pintype "passive"))
      (node (ref "U7") (pin "5") (pinfunction "DRAIN2_5") (pintype "bidirectional"))
    )
    (net (code "88") (name "Net-(U7-DRAIN3)") (class "Default")
      (node (ref "R3") (pin "1") (pinfunction "1_1") (pintype "passive"))
      (node (ref "U7") (pin "6") (pinfunction "DRAIN3_6") (pintype "bidirectional"))
    )
    (net (code "89") (name "Net-(U7-DRAIN4)") (class "Default")
      (node (ref "R10") (pin "1") (pinfunction "1_1") (pintype "passive"))
      (node (ref "U7") (pin "11") (pinfunction "DRAIN4_11") (pintype "bidirectional"))
    )
    (net (code "90") (name "Net-(U7-DRAIN5)") (class "Default")
      (node (ref "R9") (pin "1") (pinfunction "1_1") (pintype "passive"))
      (node (ref "U7") (pin "12") (pinfunction "DRAIN5_12") (pintype "bidirectional"))
    )
    (net (code "91") (name "Net-(U7-DRAIN6)") (class "Default")
      (node (ref "R8") (pin "1") (pinfunction "1_1") (pintype "passive"))
      (node (ref "U7") (pin "13") (pinfunction "DRAIN6_13") (pintype "bidirectional"))
    )
    (net (code "92") (name "Net-(U7-DRAIN7)") (class "Default")
      (node (ref "R7") (pin "1") (pinfunction "1_1") (pintype "passive"))
      (node (ref "U7") (pin "14") (pinfunction "DRAIN7_14") (pintype "bidirectional"))
    )
    (net (code "93") (name "Net-(U7-SCL)") (class "Default")
      (node (ref "L5") (pin "1") (pinfunction "1_1") (pintype "passive"))
      (node (ref "U7") (pin "15") (pinfunction "SCL_15") (pintype "bidirectional"))
    )
    (net (code "94") (name "Net-(U7-SDA)") (class "Default")
      (node (ref "L6") (pin "1") (pinfunction "1_1") (pintype "passive"))
      (node (ref "U7") (pin "2") (pinfunction "SDA_2") (pintype "bidirectional"))
    )
    (net (code "95") (name "Net-(U9-OUT)") (class "Default")
      (node (ref "R48") (pin "1") (pinfunction "1_1") (pintype "passive"))
      (node (ref "U9") (pin "5") (pinfunction "OUT_5") (pintype "output"))
    )
    (net (code "96") (name "Net-(U10-SEL)") (class "Default")
      (node (ref "R62") (pin "1") (pinfunction "1_1") (pintype "passive"))
      (node (ref "U10") (pin "11") (pinfunction "SEL_11") (pintype "bidirectional"))
    )
    (net (code "97") (name "Net-(U10-VIN)") (class "Default")
      (node (ref "R47") (pin "2") (pinfunction "2_2") (pintype "passive"))
      (node (ref "U10") (pin "2") (pinfunction "VIN_2") (pintype "bidirectional"))
    )
    (net (code "98") (name "Net-(U11-BST)") (class "Default")
      (node (ref "C4") (pin "2") (pinfunction "2_2") (pintype "passive"))
      (node (ref "U11") (pin "6") (pinfunction "BST_6") (pintype "bidirectional"))
    )
    (net (code "99") (name "Net-(U11-SW)") (class "Default")
      (node (ref "C4") (pin "1") (pinfunction "1_1") (pintype "passive"))
      (node (ref "L1") (pin "1") (pinfunction "1_1") (pintype "bidirectional"))
      (node (ref "U11") (pin "5") (pinfunction "SW_5") (pintype "bidirectional"))
    )
    (net (code "100") (name "Net-(U12-BST)") (class "Default")
      (node (ref "C29") (pin "1") (pinfunction "1_1") (pintype "passive"))
      (node (ref "U12") (pin "1") (pinfunction "BST_1") (pintype "bidirectional"))
    )
    (net (code "101") (name "Net-(U12-COMP)") (class "Default")
      (node (ref "C37") (pin "2") (pinfunction "2_2") (pintype "passive"))
      (node (ref "C38") (pin "2") (pinfunction "2_2") (pintype "passive"))
      (node (ref "U12") (pin "6") (pinfunction "COMP_6") (pintype "bidirectional"))
    )
    (net (code "102") (name "Net-(U12-FB)") (class "Default")
      (node (ref "C19") (pin "1") (pinfunction "1_1") (pintype "passive"))
      (node (ref "C65") (pin "2") (pinfunction "2_2") (pintype "passive"))
      (node (ref "R10") (pin "2") (pinfunction "2_2") (pintype "passive"))
      (node (ref "R11") (pin "1") (pinfunction "1_1") (pintype "passive"))
      (node (ref "R3") (pin "2") (pinfunction "2_2") (pintype "passive"))
      (node (ref "R30") (pin "2") (pinfunction "2_2") (pintype "passive"))
      (node (ref "R4") (pin "2") (pinfunction "2_2") (pintype "passive"))
      (node (ref "R45") (pin "2") (pinfunction "2_2") (pintype "passive"))
      (node (ref "R5") (pin "2") (pinfunction "2_2") (pintype "passive"))
      (node (ref "R6") (pin "2") (pinfunction "2_2") (pintype "passive"))
      (node (ref "R7") (pin "2") (pinfunction "2_2") (pintype "passive"))
      (node (ref "R8") (pin "2") (pinfunction "2_2") (pintype "passive"))
      (node (ref "R9") (pin "2") (pinfunction "2_2") (pintype "passive"))
      (node (ref "U12") (pin "5") (pinfunction "FB_5") (pintype "bidirectional"))
    )
    (net (code "103") (name "Net-(U12-SS)") (class "Default")
      (node (ref "C30") (pin "2") (pinfunction "2_2") (pintype "passive"))
      (node (ref "U12") (pin "4") (pinfunction "SS_4") (pintype "bidirectional"))
    )
    (net (code "104") (name "Net-(X1-CRYSTAL_2)") (class "Default")
      (node (ref "C61") (pin "2") (pinfunction "2_2") (pintype "passive"))
      (node (ref "R46") (pin "2") (pinfunction "2_2") (pintype "passive"))
      (node (ref "X1") (pin "3") (pinfunction "CRYSTAL_2_3") (pintype "bidirectional"))
    )
    (net (code "105") (name "PEDAL+") (class "Default")
      (node (ref "K1") (pin "2") (pinfunction "P$2_2") (pintype "bidirectional"))
      (node (ref "L3") (pin "1") (pinfunction "1_1") (pintype "passive"))
      (node (ref "PEDAL+") (pin "TP") (pinfunction "TP_TP") (pintype "input"))
    )
    (net (code "106") (name "PEDAL-") (class "Default")
      (node (ref "K1") (pin "1") (pinfunction "P$1_1") (pintype "bidirectional"))
      (node (ref "L4") (pin "1") (pinfunction "1_1") (pintype "passive"))
      (node (ref "PEDAL-") (pin "TP") (pinfunction "TP_TP") (pintype "input"))
    )
    (net (code "107") (name "PEDAL_IP") (class "Default")
      (node (ref "U1") (pin "11") (pinfunction "GPIO8_11") (pintype "bidirectional"))
      (node (ref "U6") (pin "4") (pinfunction "O_4") (pintype "output"))
    )
    (net (code "108") (name "QSPI_SCLK") (class "Default")
      (node (ref "U1") (pin "52") (pinfunction "QSPI_SCLK_52") (pintype "bidirectional"))
      (node (ref "U5") (pin "6") (pinfunction "CLK_6") (pintype "bidirectional"))
    )
    (net (code "109") (name "QSPI_SD0") (class "Default")
      (node (ref "U1") (pin "53") (pinfunction "QSPI_SD0_53") (pintype "bidirectional"))
      (node (ref "U5") (pin "5") (pinfunction "DI(IO0)_5") (pintype "bidirectional"))
    )
    (net (code "110") (name "QSPI_SD1") (class "Default")
      (node (ref "U1") (pin "55") (pinfunction "QSPI_SD1_55") (pintype "bidirectional"))
      (node (ref "U5") (pin "2") (pinfunction "DO(IO1)_2") (pintype "bidirectional"))
    )
    (net (code "111") (name "QSPI_SD2") (class "Default")
      (node (ref "U1") (pin "54") (pinfunction "QSPI_SD2_54") (pintype "bidirectional"))
      (node (ref "U5") (pin "3") (pinfunction "/WP_(IO2)_3") (pintype "bidirectional"))
    )
    (net (code "112") (name "QSPI_SD3") (class "Default")
      (node (ref "U1") (pin "51") (pinfunction "QSPI_SD3_51") (pintype "bidirectional"))
      (node (ref "U5") (pin "7") (pinfunction "/HOLD_OR_/RESET_(IO3)_7") (pintype "bidirectional"))
    )
    (net (code "113") (name "QSPI_SS") (class "Default")
      (node (ref "R40") (pin "1") (pinfunction "1_1") (pintype "passive"))
      (node (ref "U1") (pin "56") (pinfunction "QSPI_SS_N_56") (pintype "bidirectional"))
      (node (ref "U5") (pin "1") (pinfunction "/CS_1") (pintype "bidirectional"))
    )
    (net (code "114") (name "SAFETY_EN_DCDC") (class "Default")
      (node (ref "Q4") (pin "1") (pinfunction "G_1") (pintype "passive"))
      (node (ref "Q5") (pin "3") (pinfunction "D_3") (pintype "passive"))
      (node (ref "R27") (pin "1") (pinfunction "1_1") (pintype "passive"))
      (node (ref "R42") (pin "2") (pinfunction "2_2") (pintype "passive"))
    )
    (net (code "115") (name "SCL") (class "Default")
      (node (ref "L5") (pin "2") (pinfunction "2_2") (pintype "passive"))
      (node (ref "R58") (pin "1") (pinfunction "1_1") (pintype "passive"))
      (node (ref "R67") (pin "1") (pinfunction "1_1") (pintype "passive"))
      (node (ref "SCL") (pin "TP") (pinfunction "TP_TP") (pintype "input"))
      (node (ref "U1") (pin "7") (pinfunction "GPIO5_7") (pintype "bidirectional"))
    )
    (net (code "116") (name "SDA") (class "Default")
      (node (ref "L6") (pin "2") (pinfunction "2_2") (pintype "passive"))
      (node (ref "R60") (pin "1") (pinfunction "1_1") (pintype "passive"))
      (node (ref "R64") (pin "1") (pinfunction "1_1") (pintype "passive"))
      (node (ref "SDA") (pin "TP") (pinfunction "TP_TP") (pintype "input"))
      (node (ref "U1") (pin "6") (pinfunction "GPIO4_6") (pintype "bidirectional"))
    )
    (net (code "117") (name "VCC") (class "Default")
      (node (ref "C17") (pin "1") (pinfunction "1_1") (pintype "passive"))
      (node (ref "C18") (pin "1") (pinfunction "1_1") (pintype "passive"))
      (node (ref "C21") (pin "1") (pinfunction "1_1") (pintype "passive"))
      (node (ref "C28") (pin "2") (pinfunction "2_2") (pintype "passive"))
      (node (ref "C35") (pin "1") (pinfunction "1_1") (pintype "passive"))
      (node (ref "C63") (pin "2") (pinfunction "2_2") (pintype "passive"))
      (node (ref "C64") (pin "2") (pinfunction "2_2") (pintype "passive"))
      (node (ref "D5") (pin "1") (pinfunction "K_1") (pintype "bidirectional"))
      (node (ref "L7") (pin "1") (pinfunction "1_1") (pintype "passive"))
      (node (ref "PTC1") (pin "1") (pinfunction "1_1") (pintype "passive"))
      (node (ref "R41") (pin "2") (pinfunction "2_2") (pintype "passive"))
      (node (ref "U11") (pin "2") (pinfunction "EN_2") (pintype "bidirectional"))
      (node (ref "U11") (pin "3") (pinfunction "VIN_3") (pintype "bidirectional"))
      (node (ref "U12") (pin "2") (pinfunction "VIN_2") (pintype "bidirectional"))
    )
    (net (code "118") (name "VOUT") (class "Default")
      (node (ref "D8") (pin "1") (pinfunction "K_1") (pintype "bidirectional"))
      (node (ref "K1") (pin "5") (pinfunction "P$5_5") (pintype "bidirectional"))
      (node (ref "K1") (pin "7") (pinfunction "P$6_7") (pintype "bidirectional"))
      (node (ref "R1") (pin "2") (pinfunction "2_2") (pintype "passive"))
      (node (ref "R12") (pin "2") (pinfunction "2_2") (pintype "passive"))
      (node (ref "R37") (pin "1") (pinfunction "1_1") (pintype "passive"))
      (node (ref "VOUT") (pin "TP") (pinfunction "TP_TP") (pintype "input"))
    )
    (net (code "119") (name "XIN") (class "Default")
      (node (ref "C59") (pin "2") (pinfunction "2_2") (pintype "passive"))
      (node (ref "U1") (pin "20") (pinfunction "XIN_20") (pintype "bidirectional"))
      (node (ref "X1") (pin "1") (pinfunction "CRYSTAL_1_1") (pintype "bidirectional"))
    )
    (net (code "120") (name "XOUT") (class "Default")
      (node (ref "R46") (pin "1") (pinfunction "1_1") (pintype "passive"))
      (node (ref "U1") (pin "21") (pinfunction "XOUT_21") (pintype "bidirectional"))
    )
    (net (code "121") (name "unconnected-(D3-A-Pad1)") (class "Default")
      (node (ref "D3") (pin "1") (pinfunction "A_1") (pintype "passive"))
    )
    (net (code "122") (name "unconnected-(J1-SBU1-Pad10)") (class "Default")
      (node (ref "J1") (pin "10") (pinfunction "SBU1_10") (pintype "passive"))
    )
    (net (code "123") (name "unconnected-(J1-SBU2-Pad4)") (class "Default")
      (node (ref "J1") (pin "4") (pinfunction "SBU2_4") (pintype "passive"))
    )
    (net (code "124") (name "unconnected-(LS1-DUMMY-Pad3)") (class "Default")
      (node (ref "LS1") (pin "3") (pinfunction "DUMMY_3") (pintype "bidirectional"))
    )
    (net (code "125") (name "unconnected-(S2-Pad1)") (class "Default")
      (node (ref "S2") (pin "1") (pinfunction "1_1") (pintype "passive"))
    )
    (net (code "126") (name "unconnected-(S2-Pad3)") (class "Default")
      (node (ref "S2") (pin "3") (pinfunction "3_3") (pintype "passive"))
    )
    (net (code "127") (name "unconnected-(U1-GPIO10-Pad13)") (class "Default")
      (node (ref "U1") (pin "13") (pinfunction "GPIO10_13") (pintype "bidirectional"))
    )
    (net (code "128") (name "unconnected-(U1-GPIO11-Pad14)") (class "Default")
      (node (ref "U1") (pin "14") (pinfunction "GPIO11_14") (pintype "bidirectional"))
    )
    (net (code "129") (name "unconnected-(U1-GPIO13-Pad16)") (class "Default")
      (node (ref "U1") (pin "16") (pinfunction "GPIO13_16") (pintype "bidirectional"))
    )
    (net (code "130") (name "unconnected-(U1-GPIO14-Pad17)") (class "Default")
      (node (ref "U1") (pin "17") (pinfunction "GPIO14_17") (pintype "bidirectional"))
    )
    (net (code "131") (name "unconnected-(U1-GPIO15-Pad18)") (class "Default")
      (node (ref "U1") (pin "18") (pinfunction "GPIO15_18") (pintype "bidirectional"))
    )
    (net (code "132") (name "unconnected-(U1-GPIO20-Pad31)") (class "Default")
      (node (ref "U1") (pin "31") (pinfunction "GPIO20_31") (pintype "bidirectional"))
    )
    (net (code "133") (name "unconnected-(U1-GPIO22-Pad34)") (class "Default")
      (node (ref "U1") (pin "34") (pinfunction "GPIO22_34") (pintype "bidirectional"))
    )
    (net (code "134") (name "unconnected-(U1-GPIO23-Pad35)") (class "Default")
      (node (ref "U1") (pin "35") (pinfunction "GPIO23_35") (pintype "bidirectional"))
    )
    (net (code "135") (name "unconnected-(U1-GPIO29_{slash}_ADC3-Pad41)") (class "Default")
      (node (ref "U1") (pin "41") (pinfunction "GPIO29_/_ADC3_41") (pintype "bidirectional"))
    )
    (net (code "136") (name "unconnected-(U8-ANODE_2-Pad3)") (class "Default")
      (node (ref "U8") (pin "3") (pinfunction "ANODE_2_3") (pintype "bidirectional"))
    )
    (net (code "137") (name "unconnected-(U10-NC_1-Pad3)") (class "Default")
      (node (ref "U10") (pin "3") (pinfunction "NC_1_3") (pintype "bidirectional"))
    )
    (net (code "138") (name "unconnected-(U10-NC_2-Pad4)") (class "Default")
      (node (ref "U10") (pin "4") (pinfunction "NC_2_4") (pintype "bidirectional"))
    )
    (net (code "139") (name "unconnected-(U10-NC_3-Pad9)") (class "Default")
      (node (ref "U10") (pin "9") (pinfunction "NC_3_9") (pintype "bidirectional"))
    )
    (net (code "140") (name "unconnected-(U10-NC_4-Pad10)") (class "Default")
      (node (ref "U10") (pin "10") (pinfunction "NC_4_10") (pintype "bidirectional"))
    )
    (net (code "141") (name "unconnected-(U10-NC_5-Pad14)") (class "Default")
      (node (ref "U10") (pin "14") (pinfunction "NC_5_14") (pintype "bidirectional"))
    )
    (net (code "142") (name "unconnected-(U10-NC_6-Pad15)") (class "Default")
      (node (ref "U10") (pin "15") (pinfunction "NC_6_15") (pintype "bidirectional"))
    )
    (net (code "143") (name "unconnected-(U10-TST1-Pad6)") (class "Default")
      (node (ref "U10") (pin "6") (pinfunction "TST1_6") (pintype "bidirectional"))
    )
    (net (code "144") (name "unconnected-(U10-TST2-Pad7)") (class "Default")
      (node (ref "U10") (pin "7") (pinfunction "TST2_7") (pintype "bidirectional"))
    )
    (net (code "145") (name "unconnected-(U10-TST3-Pad8)") (class "Default")
      (node (ref "U10") (pin "8") (pinfunction "TST3_8") (pintype "bidirectional"))
    )
    (net (code "146") (name "unconnected-(U10-VBUS-Pad16)") (class "Default")
      (node (ref "U10") (pin "16") (pinfunction "VBUS_16") (pintype "bidirectional"))
    )
    (net (code "147") (name "unconnected-(U10-VBUSG-Pad1)") (class "Default")
      (node (ref "U10") (pin "1") (pinfunction "VBUSG_1") (pintype "bidirectional"))
    )
  )
)
